# Modular_RFPA_v106.net
KiCad netlist of a schematic drawn in EAGLE
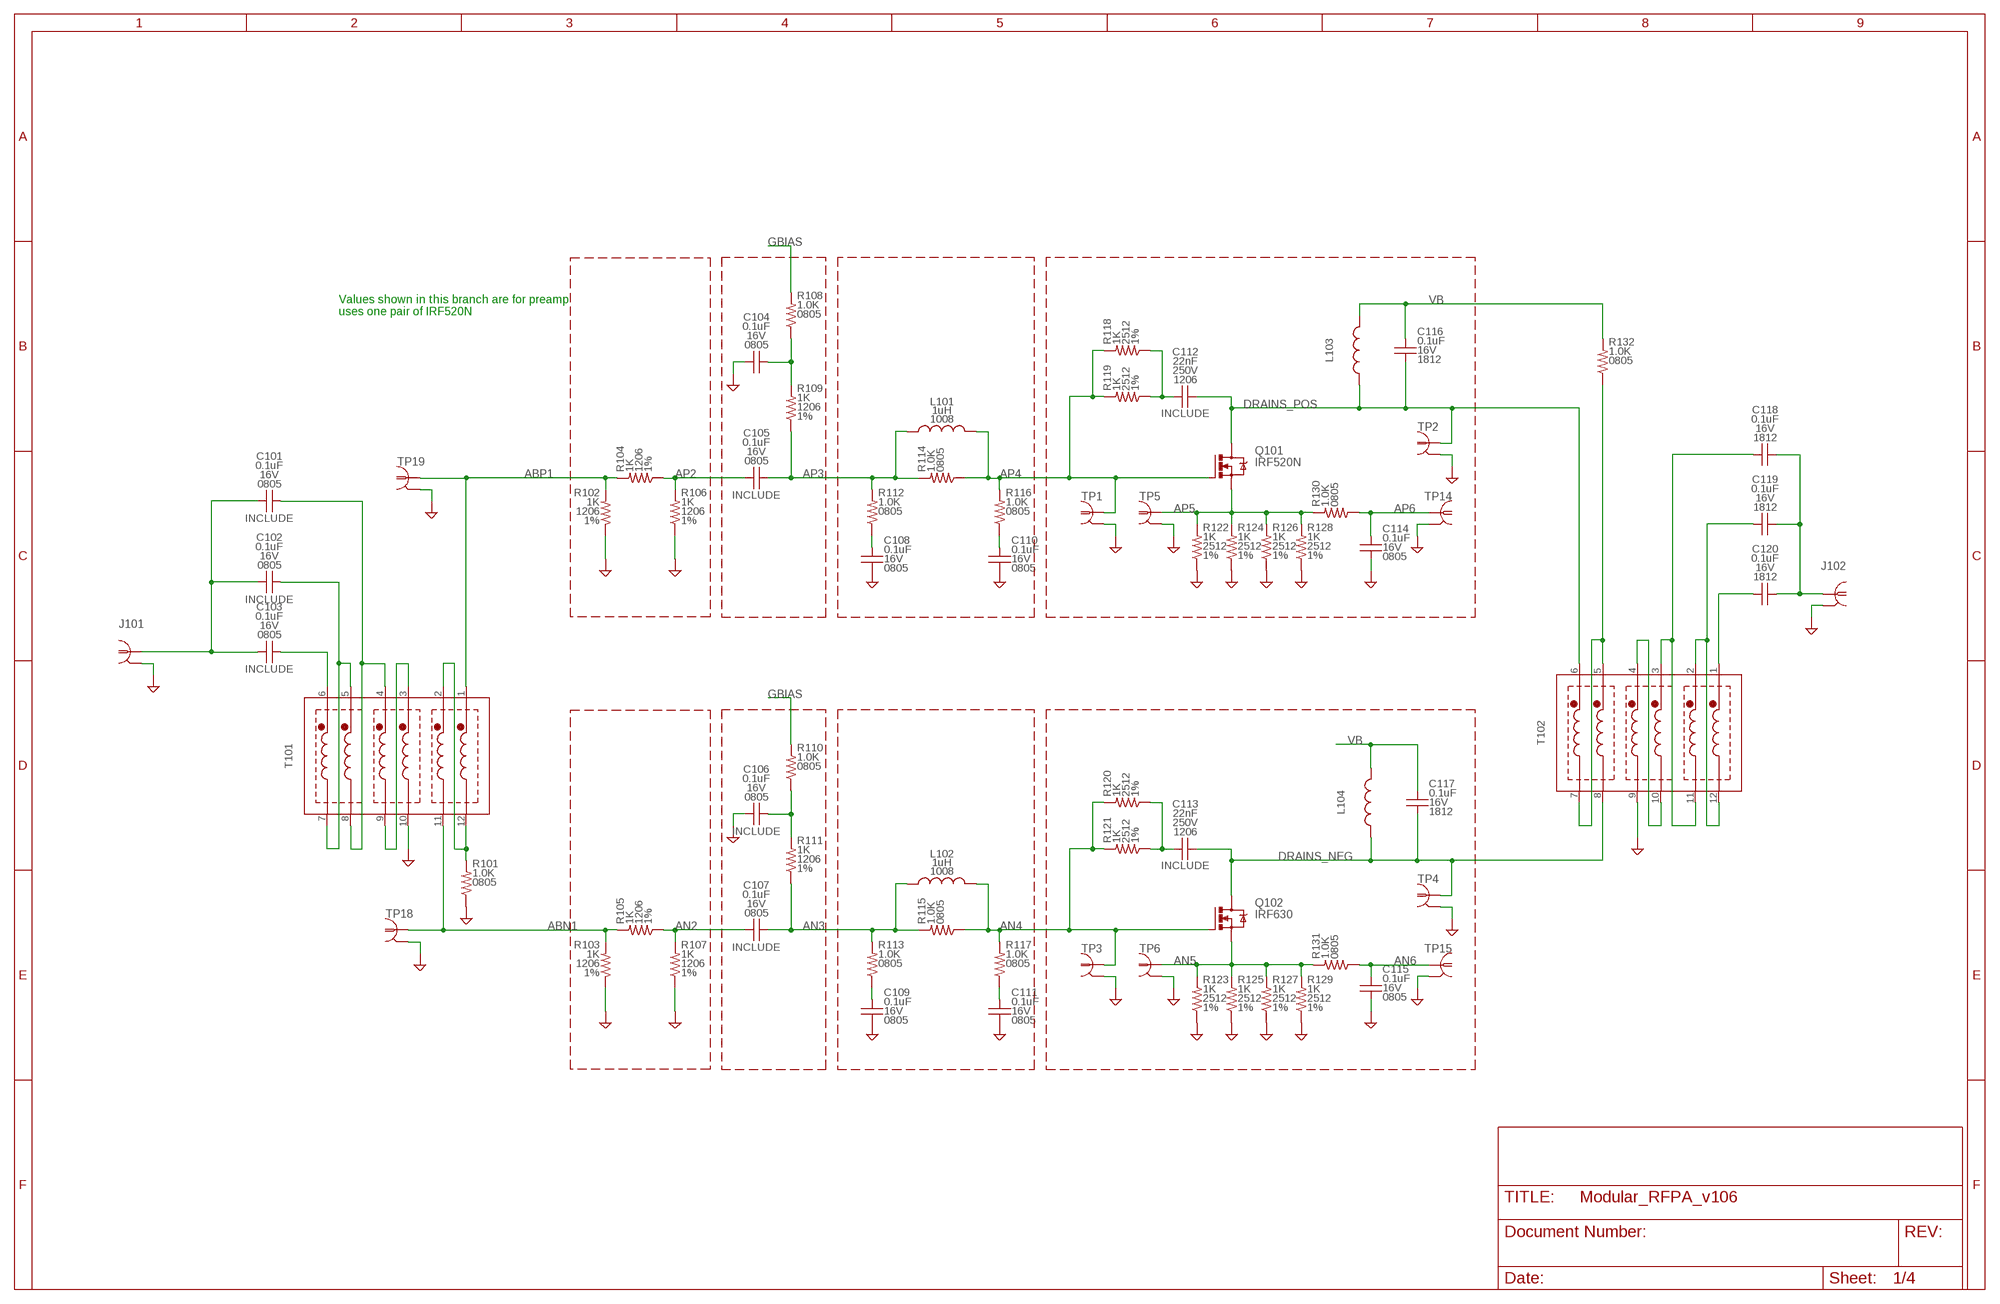
[diagram p0: schematic, sheet 1, part 1 of 2]
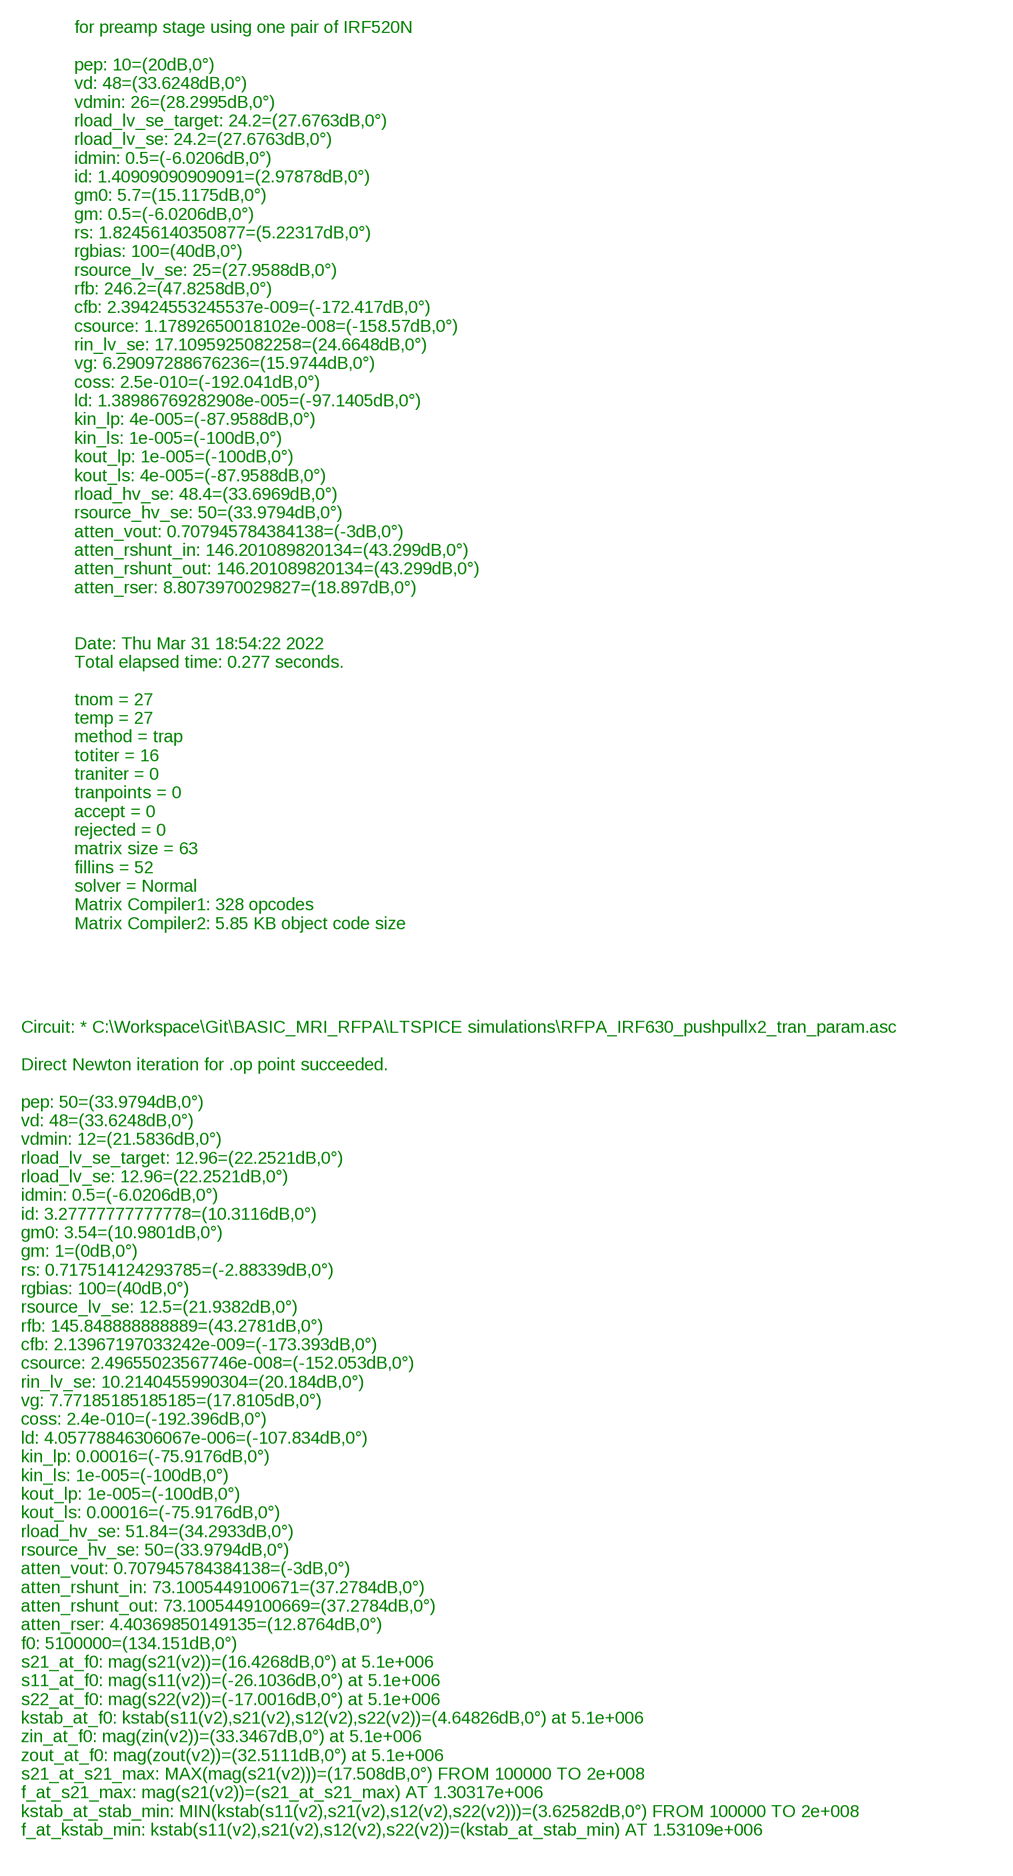
[diagram p1: schematic, sheet 1, part 2 of 2]
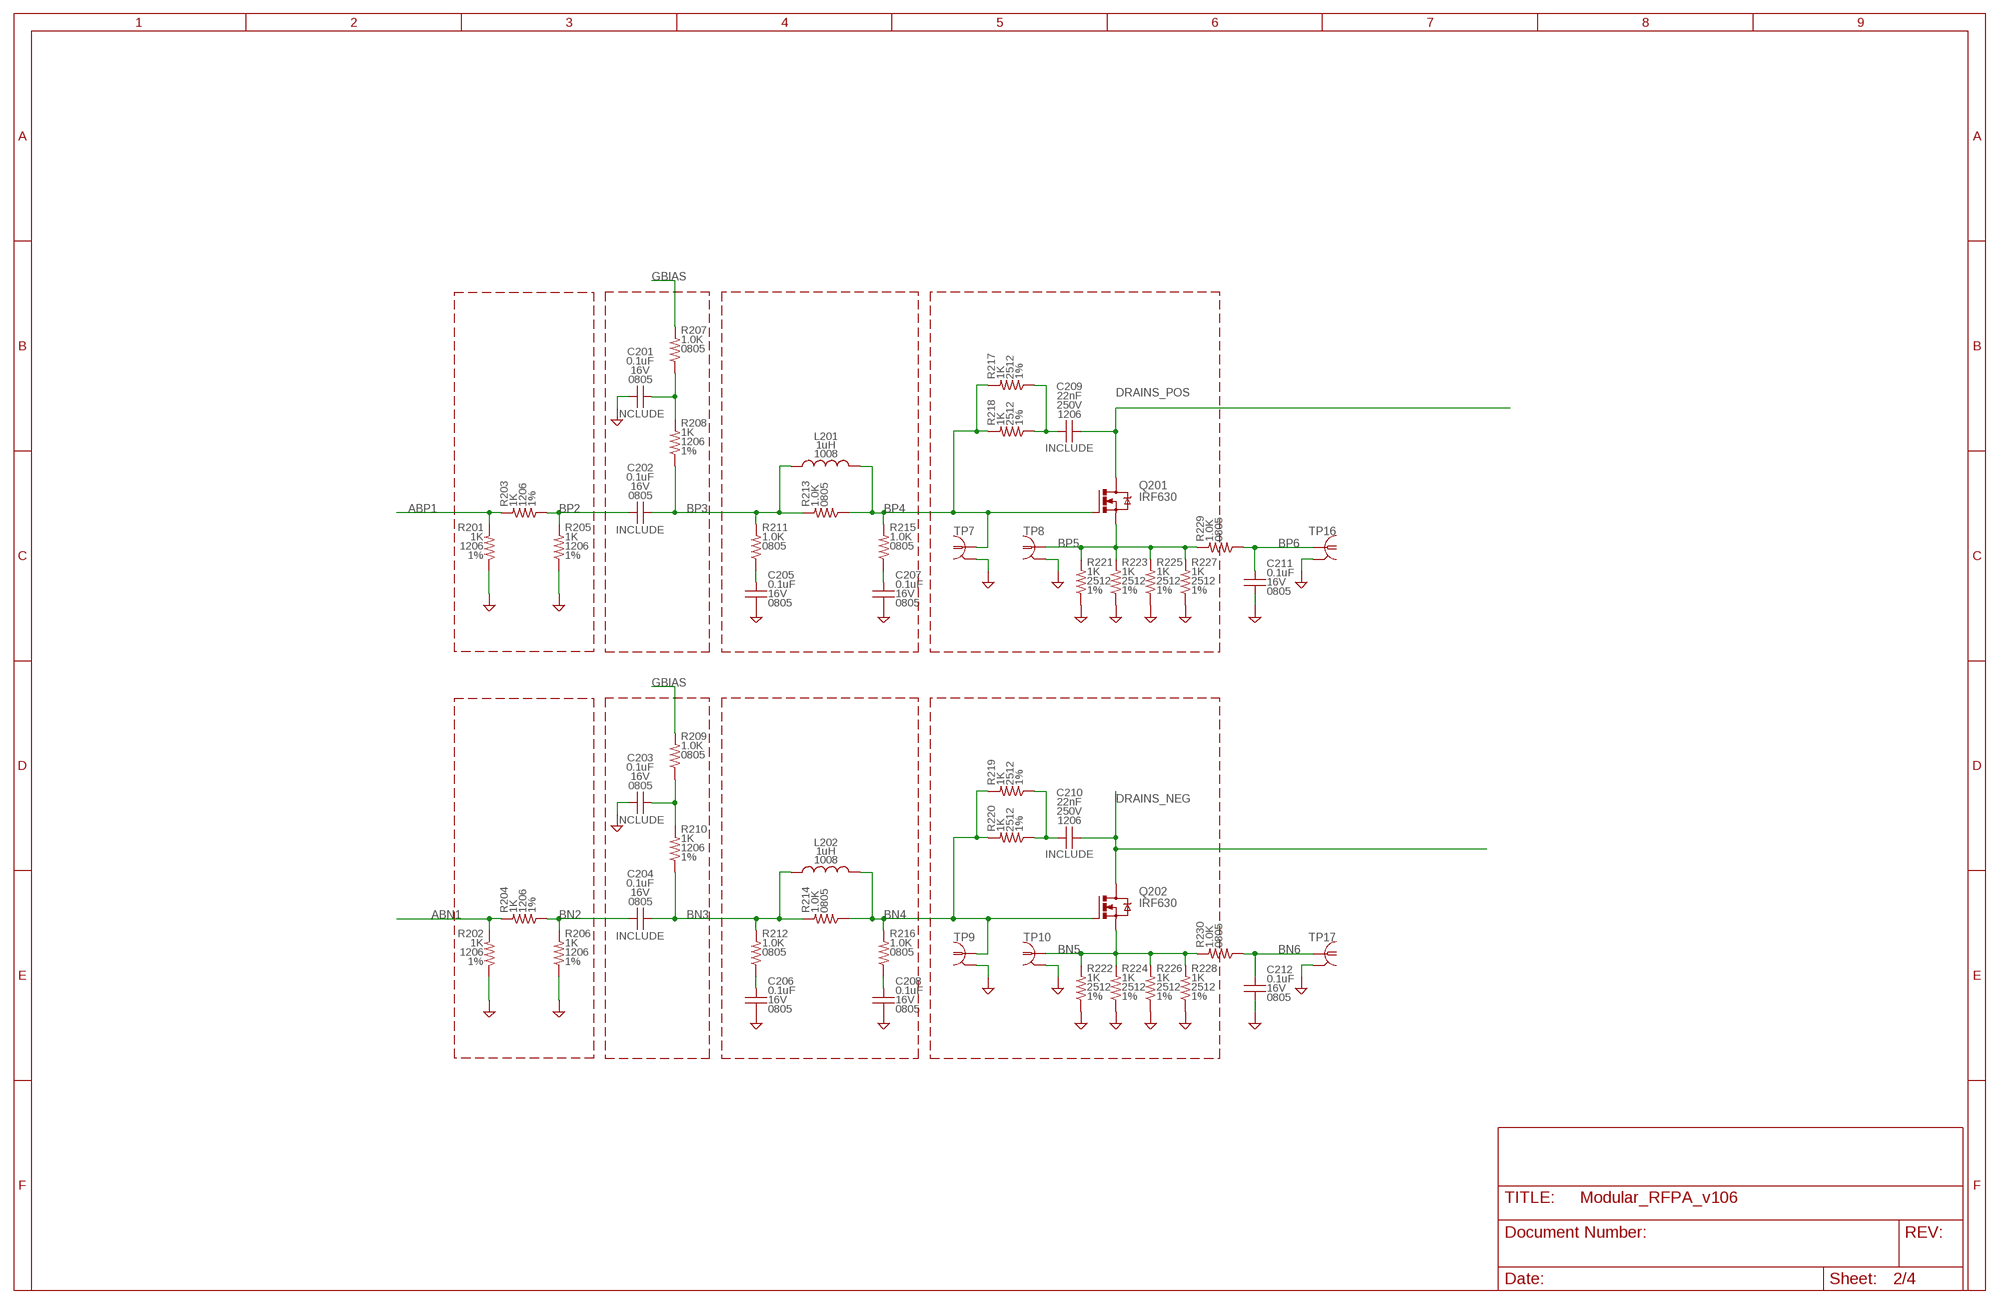
[diagram p2: schematic, sheet 2]
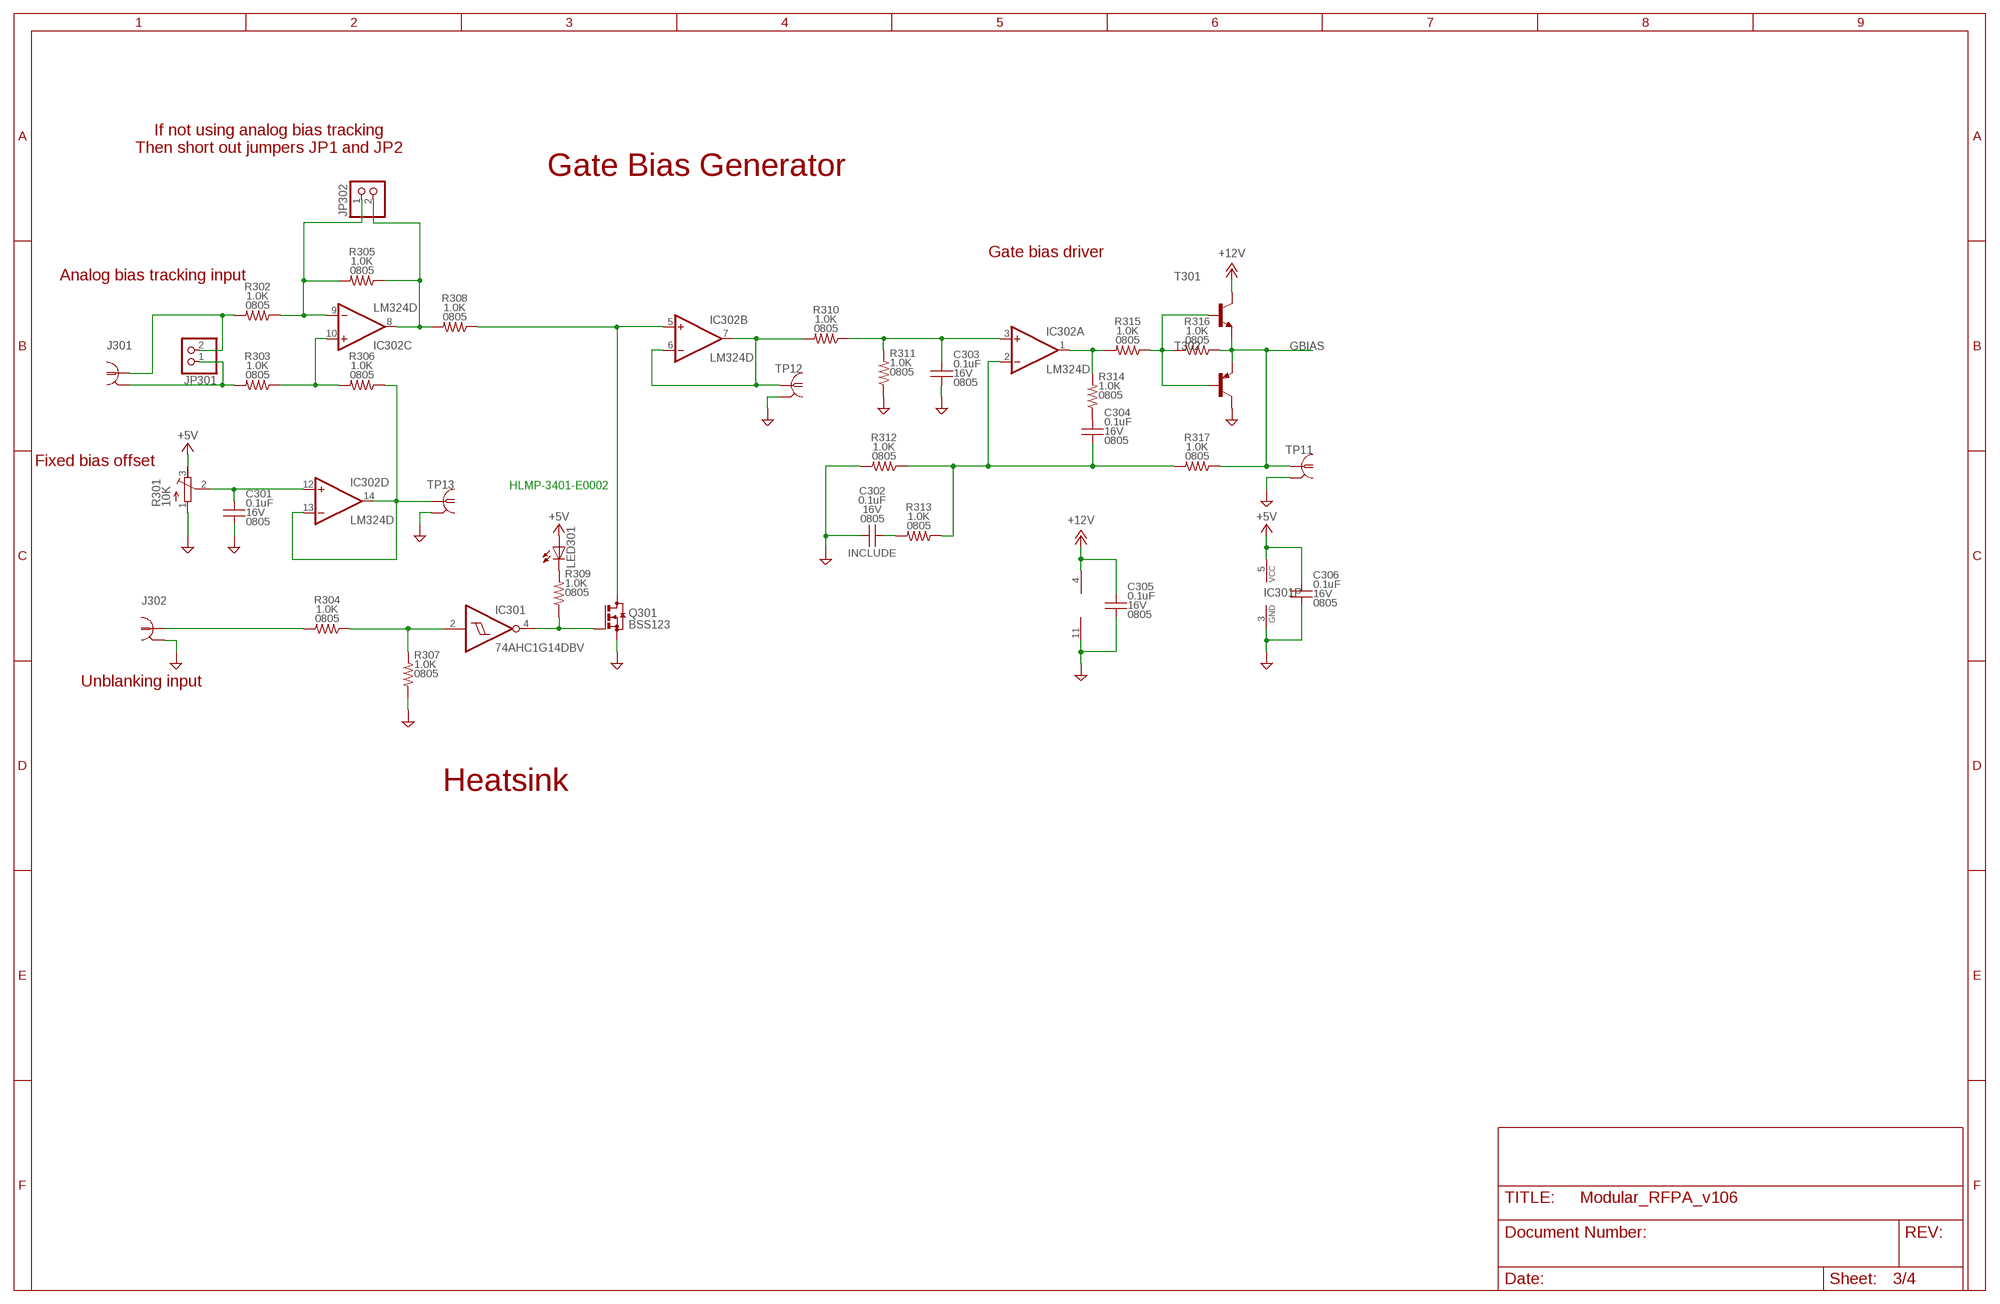
[diagram p3: schematic, sheet 3]
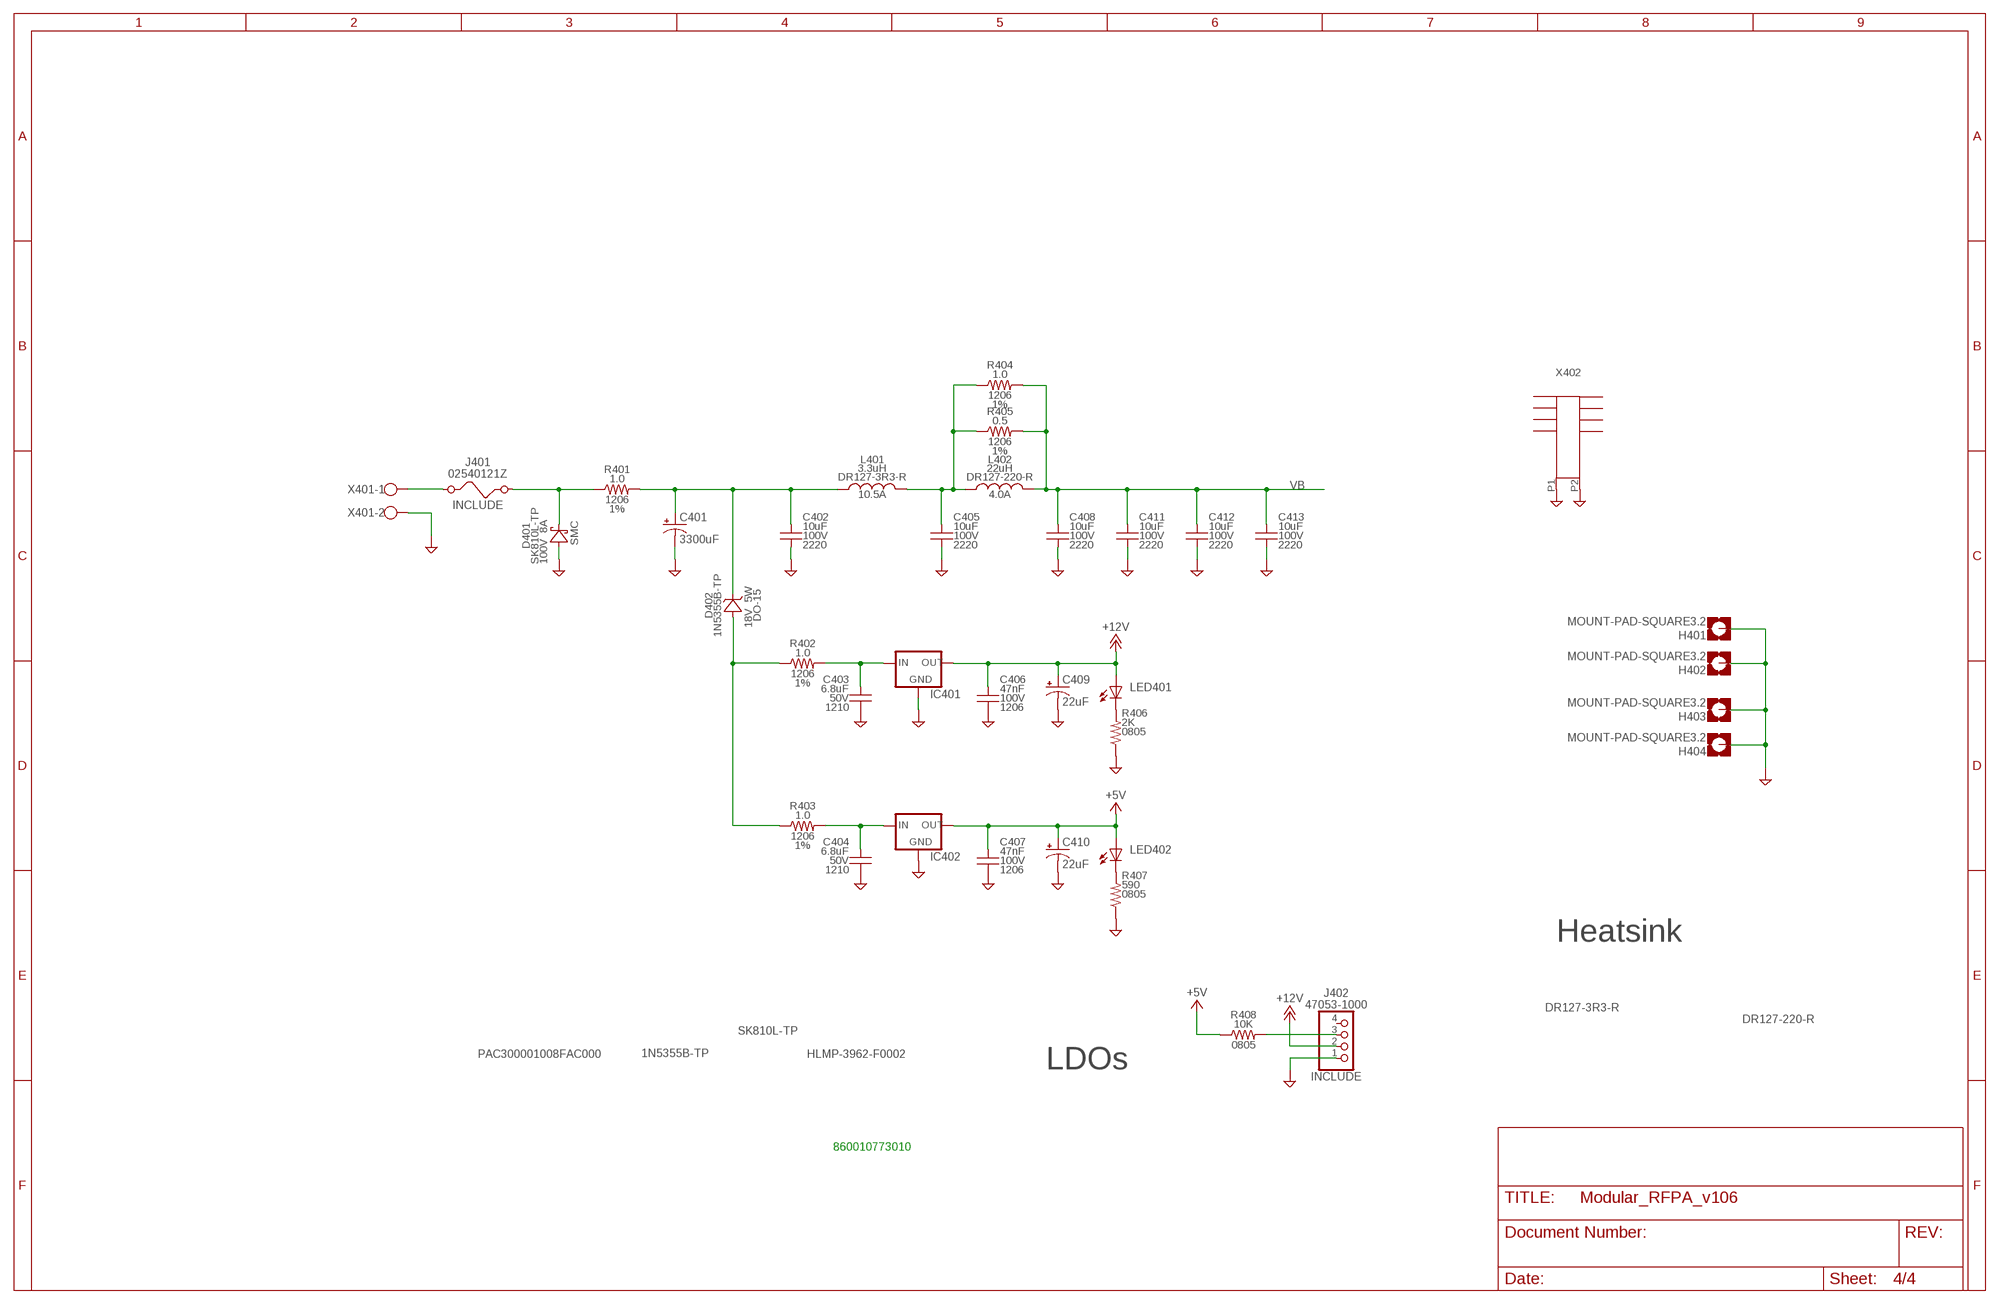
[diagram p4: schematic, sheet 4]

(export (version "E")
  (design (tool "Eeschema 10.0.6"))
  (components
    (comp (ref "C201")
      (value "0.1uF")
      (footprint "eagle-import:0805_IPC-7351B")
      (fields (field (name "PACKAGE") "0805") (field (name "VOLTAGE") "16V") (field (name "BOM") "INCLUDE"))
      (libsource (lib "eagle-import") (part "C0805_IPCC-0.1U-16V-0805-X7R"))
    )
    (comp (ref "C202")
      (value "0.1uF")
      (footprint "eagle-import:0805_IPC-7351B")
      (fields (field (name "PACKAGE") "0805") (field (name "VOLTAGE") "16V") (field (name "BOM") "INCLUDE"))
      (libsource (lib "eagle-import") (part "C0805_IPCC-0.1U-16V-0805-X7R"))
    )
    (comp (ref "C203")
      (value "0.1uF")
      (footprint "eagle-import:0805_IPC-7351B")
      (fields (field (name "PACKAGE") "0805") (field (name "VOLTAGE") "16V") (field (name "BOM") "INCLUDE"))
      (libsource (lib "eagle-import") (part "C0805_IPCC-0.1U-16V-0805-X7R"))
    )
    (comp (ref "C204")
      (value "0.1uF")
      (footprint "eagle-import:0805_IPC-7351B")
      (fields (field (name "PACKAGE") "0805") (field (name "VOLTAGE") "16V") (field (name "BOM") "INCLUDE"))
      (libsource (lib "eagle-import") (part "C0805_IPCC-0.1U-16V-0805-X7R"))
    )
    (comp (ref "C205")
      (value "0.1uF")
      (footprint "eagle-import:0805_IPC-7351B")
      (fields (field (name "VOLTAGE") "16V"))
      (libsource (lib "eagle-import") (part "C0805_IPCC-0.1U-16V-0805-X7R"))
    )
    (comp (ref "C206")
      (value "0.1uF")
      (footprint "eagle-import:0805_IPC-7351B")
      (fields (field (name "VOLTAGE") "16V"))
      (libsource (lib "eagle-import") (part "C0805_IPCC-0.1U-16V-0805-X7R"))
    )
    (comp (ref "C207")
      (value "0.1uF")
      (footprint "eagle-import:0805_IPC-7351B")
      (fields (field (name "VOLTAGE") "16V"))
      (libsource (lib "eagle-import") (part "C0805_IPCC-0.1U-16V-0805-X7R"))
    )
    (comp (ref "C208")
      (value "0.1uF")
      (footprint "eagle-import:0805_IPC-7351B")
      (fields (field (name "VOLTAGE") "16V"))
      (libsource (lib "eagle-import") (part "C0805_IPCC-0.1U-16V-0805-X7R"))
    )
    (comp (ref "C209")
      (value "22nF")
      (footprint "eagle-import:C1206")
      (fields
        (field (name "BOM") "INCLUDE")
        (field (name "PACKAGE") "1206")
        (field (name "PARTNO") "C3216NP02E223J160AA")
        (field (name "VOLTAGE") "250V")
      )
      (libsource (lib "eagle-import") (part "CC1206C-22N-250V-5%-1206-NP0"))
    )
    (comp (ref "C210")
      (value "22nF")
      (footprint "eagle-import:C1206")
      (fields
        (field (name "BOM") "INCLUDE")
        (field (name "PACKAGE") "1206")
        (field (name "PARTNO") "C3216NP02E223J160AA")
        (field (name "VOLTAGE") "250V")
      )
      (libsource (lib "eagle-import") (part "CC1206C-22N-250V-5%-1206-NP0"))
    )
    (comp (ref "C211")
      (value "0.1uF")
      (footprint "eagle-import:0805_IPC-7351B")
      (fields (field (name "VOLTAGE") "16V"))
      (libsource (lib "eagle-import") (part "C0805_IPCC-0.1U-16V-0805-X7R"))
    )
    (comp (ref "C212")
      (value "0.1uF")
      (footprint "eagle-import:0805_IPC-7351B")
      (fields (field (name "VOLTAGE") "16V"))
      (libsource (lib "eagle-import") (part "C0805_IPCC-0.1U-16V-0805-X7R"))
    )
    (comp (ref "L201")
      (value "1uH")
      (footprint "eagle-import:L1008")
      (fields (field (name "PARTNO") "1008CS-102XJEC"))
      (libsource (lib "eagle-import") (part "L_CHIP1008L-1.0U-AIR-5%-1008-0.37A"))
    )
    (comp (ref "L202")
      (value "1uH")
      (footprint "eagle-import:L1008")
      (fields (field (name "PARTNO") "1008CS-102XJEC"))
      (libsource (lib "eagle-import") (part "L_CHIP1008L-1.0U-AIR-5%-1008-0.37A"))
    )
    (comp (ref "Q201")
      (value "IRF630")
      (footprint "eagle-import:TO220BV")
      (libsource (lib "eagle-import") (part "IRF540"))
    )
    (comp (ref "Q202")
      (value "IRF630")
      (footprint "eagle-import:TO220BV")
      (libsource (lib "eagle-import") (part "IRF540"))
    )
    (comp (ref "R201")
      (value "1K")
      (footprint "eagle-import:R1206")
      (fields (field (name "POWER") "0.25"))
      (libsource (lib "eagle-import") (part "RR1206R-1.0K-1%-1206-0.25W"))
    )
    (comp (ref "R202")
      (value "1K")
      (footprint "eagle-import:R1206")
      (fields (field (name "POWER") "0.25"))
      (libsource (lib "eagle-import") (part "RR1206R-1.0K-1%-1206-0.25W"))
    )
    (comp (ref "R203")
      (value "1K")
      (footprint "eagle-import:R1206")
      (fields (field (name "POWER") "0.25"))
      (libsource (lib "eagle-import") (part "RR1206R-1.0K-1%-1206-0.25W"))
    )
    (comp (ref "R204")
      (value "1K")
      (footprint "eagle-import:R1206")
      (fields (field (name "POWER") "0.25"))
      (libsource (lib "eagle-import") (part "RR1206R-1.0K-1%-1206-0.25W"))
    )
    (comp (ref "R205")
      (value "1K")
      (footprint "eagle-import:R1206")
      (fields (field (name "POWER") "0.25"))
      (libsource (lib "eagle-import") (part "RR1206R-1.0K-1%-1206-0.25W"))
    )
    (comp (ref "R206")
      (value "1K")
      (footprint "eagle-import:R1206")
      (fields (field (name "POWER") "0.25"))
      (libsource (lib "eagle-import") (part "RR1206R-1.0K-1%-1206-0.25W"))
    )
    (comp (ref "R207")
      (value "1.0K")
      (footprint "eagle-import:0805_IPC-7351B")
      (libsource (lib "eagle-import") (part "R0805_IPCR-1.0K-0.1%-0805-0.1W"))
    )
    (comp (ref "R208")
      (value "1K")
      (footprint "eagle-import:R1206")
      (fields (field (name "POWER") "0.25"))
      (libsource (lib "eagle-import") (part "RR1206R-1.0K-1%-1206-0.25W"))
    )
    (comp (ref "R209")
      (value "1.0K")
      (footprint "eagle-import:0805_IPC-7351B")
      (libsource (lib "eagle-import") (part "R0805_IPCR-1.0K-0.1%-0805-0.1W"))
    )
    (comp (ref "R210")
      (value "1K")
      (footprint "eagle-import:R1206")
      (fields (field (name "POWER") "0.25"))
      (libsource (lib "eagle-import") (part "RR1206R-1.0K-1%-1206-0.25W"))
    )
    (comp (ref "R211")
      (value "1.0K")
      (footprint "eagle-import:0805_IPC-7351B")
      (libsource (lib "eagle-import") (part "R0805_IPCR-1.0K-0.1%-0805-0.1W"))
    )
    (comp (ref "R212")
      (value "1.0K")
      (footprint "eagle-import:0805_IPC-7351B")
      (libsource (lib "eagle-import") (part "R0805_IPCR-1.0K-0.1%-0805-0.1W"))
    )
    (comp (ref "R213")
      (value "1.0K")
      (footprint "eagle-import:0805_IPC-7351B")
      (libsource (lib "eagle-import") (part "R0805_IPCR-1.0K-0.1%-0805-0.1W"))
    )
    (comp (ref "R214")
      (value "1.0K")
      (footprint "eagle-import:0805_IPC-7351B")
      (libsource (lib "eagle-import") (part "R0805_IPCR-1.0K-0.1%-0805-0.1W"))
    )
    (comp (ref "R215")
      (value "1.0K")
      (footprint "eagle-import:0805_IPC-7351B")
      (libsource (lib "eagle-import") (part "R0805_IPCR-1.0K-0.1%-0805-0.1W"))
    )
    (comp (ref "R216")
      (value "1.0K")
      (footprint "eagle-import:0805_IPC-7351B")
      (libsource (lib "eagle-import") (part "R0805_IPCR-1.0K-0.1%-0805-0.1W"))
    )
    (comp (ref "R217")
      (value "1K")
      (footprint "eagle-import:R2512")
      (fields (field (name "POWER") "1"))
      (libsource (lib "eagle-import") (part "RR2512R-1K-1%-2512-1W"))
    )
    (comp (ref "R218")
      (value "1K")
      (footprint "eagle-import:R2512")
      (fields (field (name "POWER") "1"))
      (libsource (lib "eagle-import") (part "RR2512R-1K-1%-2512-1W"))
    )
    (comp (ref "R219")
      (value "1K")
      (footprint "eagle-import:R2512")
      (fields (field (name "POWER") "1"))
      (libsource (lib "eagle-import") (part "RR2512R-1K-1%-2512-1W"))
    )
    (comp (ref "R220")
      (value "1K")
      (footprint "eagle-import:R2512")
      (fields (field (name "POWER") "1"))
      (libsource (lib "eagle-import") (part "RR2512R-1K-1%-2512-1W"))
    )
    (comp (ref "R221")
      (value "1K")
      (footprint "eagle-import:R2512")
      (fields (field (name "POWER") "1"))
      (libsource (lib "eagle-import") (part "RR2512R-1K-1%-2512-1W"))
    )
    (comp (ref "R222")
      (value "1K")
      (footprint "eagle-import:R2512")
      (fields (field (name "POWER") "1"))
      (libsource (lib "eagle-import") (part "RR2512R-1K-1%-2512-1W"))
    )
    (comp (ref "R223")
      (value "1K")
      (footprint "eagle-import:R2512")
      (fields (field (name "POWER") "1"))
      (libsource (lib "eagle-import") (part "RR2512R-1K-1%-2512-1W"))
    )
    (comp (ref "R224")
      (value "1K")
      (footprint "eagle-import:R2512")
      (fields (field (name "POWER") "1"))
      (libsource (lib "eagle-import") (part "RR2512R-1K-1%-2512-1W"))
    )
    (comp (ref "R225")
      (value "1K")
      (footprint "eagle-import:R2512")
      (fields (field (name "POWER") "1"))
      (libsource (lib "eagle-import") (part "RR2512R-1K-1%-2512-1W"))
    )
    (comp (ref "R226")
      (value "1K")
      (footprint "eagle-import:R2512")
      (fields (field (name "POWER") "1"))
      (libsource (lib "eagle-import") (part "RR2512R-1K-1%-2512-1W"))
    )
    (comp (ref "R227")
      (value "1K")
      (footprint "eagle-import:R2512")
      (fields (field (name "POWER") "1"))
      (libsource (lib "eagle-import") (part "RR2512R-1K-1%-2512-1W"))
    )
    (comp (ref "R228")
      (value "1K")
      (footprint "eagle-import:R2512")
      (fields (field (name "POWER") "1"))
      (libsource (lib "eagle-import") (part "RR2512R-1K-1%-2512-1W"))
    )
    (comp (ref "R229")
      (value "1.0K")
      (footprint "eagle-import:0805_IPC-7351B")
      (libsource (lib "eagle-import") (part "R0805_IPCR-1.0K-0.1%-0805-0.1W"))
    )
    (comp (ref "R230")
      (value "1.0K")
      (footprint "eagle-import:0805_IPC-7351B")
      (libsource (lib "eagle-import") (part "R0805_IPCR-1.0K-0.1%-0805-0.1W"))
    )
    (comp (ref "TP7")
      (value "PROBE_TPTP_5MM")
      (footprint "eagle-import:PROBE_TP_5MM")
      (libsource (lib "eagle-import") (part "PROBE_TPTP_5MM"))
    )
    (comp (ref "TP8")
      (value "PROBE_TPTP_7P5MM")
      (footprint "eagle-import:PROBE_TP_7P5MM")
      (libsource (lib "eagle-import") (part "PROBE_TPTP_7P5MM"))
    )
    (comp (ref "TP9")
      (value "PROBE_TPTP_5MM")
      (footprint "eagle-import:PROBE_TP_5MM")
      (libsource (lib "eagle-import") (part "PROBE_TPTP_5MM"))
    )
    (comp (ref "TP10")
      (value "PROBE_TPTP_5MM")
      (footprint "eagle-import:PROBE_TP_5MM")
      (libsource (lib "eagle-import") (part "PROBE_TPTP_5MM"))
    )
    (comp (ref "TP16")
      (value "PROBE_TPTP_5MM")
      (footprint "eagle-import:PROBE_TP_5MM")
      (libsource (lib "eagle-import") (part "PROBE_TPTP_5MM"))
    )
    (comp (ref "TP17")
      (value "PROBE_TPTP_7P5MM")
      (footprint "eagle-import:PROBE_TP_7P5MM")
      (libsource (lib "eagle-import") (part "PROBE_TPTP_7P5MM"))
    )
    (comp (ref "C301")
      (value "0.1uF")
      (footprint "eagle-import:0805_IPC-7351B")
      (fields (field (name "VOLTAGE") "16V"))
      (libsource (lib "eagle-import") (part "C0805_IPCC-0.1U-16V-0805-X7R"))
    )
    (comp (ref "C302")
      (value "0.1uF")
      (footprint "eagle-import:0805_IPC-7351B")
      (fields (field (name "PACKAGE") "0805") (field (name "VOLTAGE") "16V") (field (name "BOM") "INCLUDE"))
      (libsource (lib "eagle-import") (part "C0805_IPCC-0.1U-16V-0805-X7R"))
    )
    (comp (ref "C303")
      (value "0.1uF")
      (footprint "eagle-import:0805_IPC-7351B")
      (fields (field (name "VOLTAGE") "16V"))
      (libsource (lib "eagle-import") (part "C0805_IPCC-0.1U-16V-0805-X7R"))
    )
    (comp (ref "C304")
      (value "0.1uF")
      (footprint "eagle-import:0805_IPC-7351B")
      (fields (field (name "VOLTAGE") "16V"))
      (libsource (lib "eagle-import") (part "C0805_IPCC-0.1U-16V-0805-X7R"))
    )
    (comp (ref "C305")
      (value "0.1uF")
      (footprint "eagle-import:0805_IPC-7351B")
      (fields (field (name "VOLTAGE") "16V"))
      (libsource (lib "eagle-import") (part "C0805_IPCC-0.1U-16V-0805-X7R"))
    )
    (comp (ref "C306")
      (value "0.1uF")
      (footprint "eagle-import:0805_IPC-7351B")
      (fields (field (name "VOLTAGE") "16V"))
      (libsource (lib "eagle-import") (part "C0805_IPCC-0.1U-16V-0805-X7R"))
    )
    (comp (ref "IC301")
      (value "74AHC1G14DBV")
      (footprint "eagle-import:SOT23-5")
      (libsource (lib "eagle-import") (part "741G14DBVAHC"))
    )
    (comp (ref "IC302")
      (value "LM324D")
      (footprint "eagle-import:SO14")
      (libsource (lib "eagle-import") (part "LM324D"))
    )
    (comp (ref "J301")
      (value "COAXBNC_EDGE")
      (footprint "eagle-import:BNC_EDGE")
      (libsource (lib "eagle-import") (part "COAXBNC_EDGE"))
    )
    (comp (ref "J302")
      (value "COAXBNC_EDGE")
      (footprint "eagle-import:BNC_EDGE")
      (libsource (lib "eagle-import") (part "COAXBNC_EDGE"))
    )
    (comp (ref "JP301")
      (value "PINHD-1X2")
      (footprint "eagle-import:1X02")
      (libsource (lib "eagle-import") (part "PINHD-1X2"))
    )
    (comp (ref "JP302")
      (value "PINHD-1X2")
      (footprint "eagle-import:1X02")
      (libsource (lib "eagle-import") (part "PINHD-1X2"))
    )
    (comp (ref "LED301")
      (value "LED5MM")
      (footprint "eagle-import:LED5MM")
      (libsource (lib "eagle-import") (part "LED5MM"))
    )
    (comp (ref "Q301")
      (value "BSS123")
      (footprint "eagle-import:SOT23")
      (libsource (lib "eagle-import") (part "BSS123"))
    )
    (comp (ref "R301")
      (value "10K")
      (footprint "eagle-import:RTRIM3299W")
      (libsource (lib "eagle-import") (part "R-TRIMM3299W"))
    )
    (comp (ref "R302")
      (value "1.0K")
      (footprint "eagle-import:0805_IPC-7351B")
      (fields (field (name "PACKAGE") "0805"))
      (libsource (lib "eagle-import") (part "R0805_IPCR-1.0K-0.1%-0805-0.1W"))
    )
    (comp (ref "R303")
      (value "1.0K")
      (footprint "eagle-import:0805_IPC-7351B")
      (fields (field (name "PACKAGE") "0805"))
      (libsource (lib "eagle-import") (part "R0805_IPCR-1.0K-0.1%-0805-0.1W"))
    )
    (comp (ref "R304")
      (value "1.0K")
      (footprint "eagle-import:0805_IPC-7351B")
      (fields (field (name "PACKAGE") "0805"))
      (libsource (lib "eagle-import") (part "R0805_IPCR-1.0K-0.1%-0805-0.1W"))
    )
    (comp (ref "R305")
      (value "1.0K")
      (footprint "eagle-import:0805_IPC-7351B")
      (fields (field (name "PACKAGE") "0805"))
      (libsource (lib "eagle-import") (part "R0805_IPCR-1.0K-0.1%-0805-0.1W"))
    )
    (comp (ref "R306")
      (value "1.0K")
      (footprint "eagle-import:0805_IPC-7351B")
      (fields (field (name "PACKAGE") "0805"))
      (libsource (lib "eagle-import") (part "R0805_IPCR-1.0K-0.1%-0805-0.1W"))
    )
    (comp (ref "R307")
      (value "1.0K")
      (footprint "eagle-import:0805_IPC-7351B")
      (libsource (lib "eagle-import") (part "R0805_IPCR-1.0K-0.1%-0805-0.1W"))
    )
    (comp (ref "R308")
      (value "1.0K")
      (footprint "eagle-import:0805_IPC-7351B")
      (fields (field (name "PACKAGE") "0805"))
      (libsource (lib "eagle-import") (part "R0805_IPCR-1.0K-0.1%-0805-0.1W"))
    )
    (comp (ref "R309")
      (value "1.0K")
      (footprint "eagle-import:0805_IPC-7351B")
      (libsource (lib "eagle-import") (part "R0805_IPCR-1.0K-0.1%-0805-0.1W"))
    )
    (comp (ref "R310")
      (value "1.0K")
      (footprint "eagle-import:0805_IPC-7351B")
      (fields (field (name "PACKAGE") "0805"))
      (libsource (lib "eagle-import") (part "R0805_IPCR-1.0K-0.1%-0805-0.1W"))
    )
    (comp (ref "R311")
      (value "1.0K")
      (footprint "eagle-import:0805_IPC-7351B")
      (libsource (lib "eagle-import") (part "R0805_IPCR-1.0K-0.1%-0805-0.1W"))
    )
    (comp (ref "R312")
      (value "1.0K")
      (footprint "eagle-import:0805_IPC-7351B")
      (fields (field (name "PACKAGE") "0805"))
      (libsource (lib "eagle-import") (part "R0805_IPCR-1.0K-0.1%-0805-0.1W"))
    )
    (comp (ref "R313")
      (value "1.0K")
      (footprint "eagle-import:0805_IPC-7351B")
      (fields (field (name "PACKAGE") "0805"))
      (libsource (lib "eagle-import") (part "R0805_IPCR-1.0K-0.1%-0805-0.1W"))
    )
    (comp (ref "R314")
      (value "1.0K")
      (footprint "eagle-import:0805_IPC-7351B")
      (libsource (lib "eagle-import") (part "R0805_IPCR-1.0K-0.1%-0805-0.1W"))
    )
    (comp (ref "R315")
      (value "1.0K")
      (footprint "eagle-import:0805_IPC-7351B")
      (fields (field (name "PACKAGE") "0805"))
      (libsource (lib "eagle-import") (part "R0805_IPCR-1.0K-0.1%-0805-0.1W"))
    )
    (comp (ref "R316")
      (value "1.0K")
      (footprint "eagle-import:0805_IPC-7351B")
      (fields (field (name "PACKAGE") "0805"))
      (libsource (lib "eagle-import") (part "R0805_IPCR-1.0K-0.1%-0805-0.1W"))
    )
    (comp (ref "R317")
      (value "1.0K")
      (footprint "eagle-import:0805_IPC-7351B")
      (fields (field (name "PACKAGE") "0805"))
      (libsource (lib "eagle-import") (part "R0805_IPCR-1.0K-0.1%-0805-0.1W"))
    )
    (comp (ref "T301")
      (value "BC808-NPN-SOT23-BEC")
      (footprint "eagle-import:SOT23-BEC")
      (libsource (lib "eagle-import") (part "-NPN-SOT23-BECBC808"))
    )
    (comp (ref "T302")
      (value "BC807-16-PNP-SOT23-BEC")
      (footprint "eagle-import:SOT23-BEC")
      (libsource (lib "eagle-import") (part "-PNP-SOT23-BECBC807-16"))
    )
    (comp (ref "TP11")
      (value "PROBE_TPTP_5MM")
      (footprint "eagle-import:PROBE_TP_5MM")
      (libsource (lib "eagle-import") (part "PROBE_TPTP_5MM"))
    )
    (comp (ref "TP12")
      (value "PROBE_TPTP_5MM")
      (footprint "eagle-import:PROBE_TP_5MM")
      (libsource (lib "eagle-import") (part "PROBE_TPTP_5MM"))
    )
    (comp (ref "TP13")
      (value "PROBE_TPTP_5MM")
      (footprint "eagle-import:PROBE_TP_5MM")
      (libsource (lib "eagle-import") (part "PROBE_TPTP_5MM"))
    )
    (comp (ref "C401")
      (value "3300uF")
      (footprint "eagle-import:EB25D")
      (libsource (lib "eagle-import") (part "CPOL-USE10-25"))
    )
    (comp (ref "C402")
      (value "10uF")
      (footprint "eagle-import:C2220_CKG57N")
      (fields
        (field (name "BOM") "INCLUDE")
        (field (name "PACKAGE") "2220")
        (field (name "PARTNO") "CGA9N3X7S2A106M230KE")
        (field (name "VOLTAGE") "100V")
      )
      (libsource (lib "eagle-import") (part "CC2220_CKG57NCC-10U-100V-20%-2220-X7T"))
    )
    (comp (ref "C403")
      (value "6.8uF")
      (footprint "eagle-import:C1210")
      (fields (field (name "PARTNO") "CGA6P3X7S1H685K250AB") (field (name "VOLTAGE") "50V"))
      (libsource (lib "eagle-import") (part "CC1210CC-6.8U-50V-10%-1210-X7S"))
    )
    (comp (ref "C404")
      (value "6.8uF")
      (footprint "eagle-import:C1210")
      (fields (field (name "PARTNO") "CGA6P3X7S1H685K250AB") (field (name "VOLTAGE") "50V"))
      (libsource (lib "eagle-import") (part "CC1210CC-6.8U-50V-10%-1210-X7S"))
    )
    (comp (ref "C405")
      (value "10uF")
      (footprint "eagle-import:C2220_CKG57N")
      (fields
        (field (name "BOM") "INCLUDE")
        (field (name "PACKAGE") "2220")
        (field (name "PARTNO") "CGA9N3X7S2A106M230KE")
        (field (name "VOLTAGE") "100V")
      )
      (libsource (lib "eagle-import") (part "CC2220_CKG57NCC-10U-100V-20%-2220-X7T"))
    )
    (comp (ref "C406")
      (value "47nF")
      (footprint "eagle-import:C1206")
      (fields (field (name "PARTNO") "C3216C0G2A473J115AC") (field (name "VOLTAGE") "100V"))
      (libsource (lib "eagle-import") (part "CC1206C-47N-100V-5%-1206-NP0"))
    )
    (comp (ref "C407")
      (value "47nF")
      (footprint "eagle-import:C1206")
      (fields (field (name "PARTNO") "C3216C0G2A473J115AC") (field (name "VOLTAGE") "100V"))
      (libsource (lib "eagle-import") (part "CC1206C-47N-100V-5%-1206-NP0"))
    )
    (comp (ref "C408")
      (value "10uF")
      (footprint "eagle-import:C2220_CKG57N")
      (fields (field (name "PARTNO") "CGA9N3X7S2A106M230KE") (field (name "VOLTAGE") "100V"))
      (libsource (lib "eagle-import") (part "CC2220_CKG57NCC-10U-100V-20%-2220-X7T"))
    )
    (comp (ref "C409")
      (value "22uF")
      (footprint "eagle-import:E2,5-7")
      (libsource (lib "eagle-import") (part "CPOL-USE2.5-7"))
    )
    (comp (ref "C410")
      (value "22uF")
      (footprint "eagle-import:E2,5-7")
      (libsource (lib "eagle-import") (part "CPOL-USE2.5-7"))
    )
    (comp (ref "C411")
      (value "10uF")
      (footprint "eagle-import:C2220_CKG57N")
      (fields (field (name "PARTNO") "CGA9N3X7S2A106M230KE") (field (name "VOLTAGE") "100V"))
      (libsource (lib "eagle-import") (part "CC2220_CKG57NCC-10U-100V-20%-2220-X7T"))
    )
    (comp (ref "C412")
      (value "10uF")
      (footprint "eagle-import:C2220_CKG57N")
      (fields (field (name "PARTNO") "CGA9N3X7S2A106M230KE") (field (name "VOLTAGE") "100V"))
      (libsource (lib "eagle-import") (part "CC2220_CKG57NCC-10U-100V-20%-2220-X7T"))
    )
    (comp (ref "C413")
      (value "10uF")
      (footprint "eagle-import:C2220_CKG57N")
      (fields (field (name "PARTNO") "CGA9N3X7S2A106M230KE") (field (name "VOLTAGE") "100V"))
      (libsource (lib "eagle-import") (part "CC2220_CKG57NCC-10U-100V-20%-2220-X7T"))
    )
    (comp (ref "D401")
      (value "D-SCHOTTKYSK810L-TPSMC")
      (footprint "eagle-import:DO-214AB(SMC)")
      (fields (field (name "PARTNO") "SK810L-TP") (field (name "VOLTAGE") "100V"))
      (libsource (lib "eagle-import") (part "D-SCHOTTKYSMCSK810L-TP"))
    )
    (comp (ref "D402")
      (value "D-ZENER1N5355B-TPDO15-12")
      (footprint "eagle-import:DO15-12")
      (fields (field (name "PARTNO") "1N5355B-TP") (field (name "POWER") "5W") (field (name "VOLTAGE") "18V"))
      (libsource (lib "eagle-import") (part "D-ZENERDO15-121N5355B-TP"))
    )
    (comp (ref "H401")
      (value "MOUNT-PAD-SQUARE3.2")
      (footprint "eagle-import:3,2-PAD-SQUARE")
      (libsource (lib "eagle-import") (part "MOUNT-PAD-SQUARE3.2"))
    )
    (comp (ref "H402")
      (value "MOUNT-PAD-SQUARE3.2")
      (footprint "eagle-import:3,2-PAD-SQUARE")
      (libsource (lib "eagle-import") (part "MOUNT-PAD-SQUARE3.2"))
    )
    (comp (ref "H403")
      (value "MOUNT-PAD-SQUARE3.2")
      (footprint "eagle-import:3,2-PAD-SQUARE")
      (libsource (lib "eagle-import") (part "MOUNT-PAD-SQUARE3.2"))
    )
    (comp (ref "H404")
      (value "MOUNT-PAD-SQUARE3.2")
      (footprint "eagle-import:3,2-PAD-SQUARE")
      (libsource (lib "eagle-import") (part "MOUNT-PAD-SQUARE3.2"))
    )
    (comp (ref "IC401")
      (value "78XXS")
      (footprint "eagle-import:78XXS")
      (libsource (lib "eagle-import") (part "78XXS"))
    )
    (comp (ref "IC402")
      (value "78XXS")
      (footprint "eagle-import:78XXS")
      (libsource (lib "eagle-import") (part "78XXS"))
    )
    (comp (ref "J401")
      (value "FUSE_2P")
      (footprint "eagle-import:02540121Z")
      (fields (field (name "PARTNO") "02540121Z"))
      (libsource (lib "eagle-import") (part "FUSE_2P"))
    )
    (comp (ref "J402")
      (value "KK_PCFAN")
      (footprint "eagle-import:47053-1000")
      (fields (field (name "PARTNO") "47053-1000"))
      (libsource (lib "eagle-import") (part "KK_PCFAN"))
    )
    (comp (ref "L401")
      (value "3.3uH")
      (footprint "eagle-import:DR127")
      (fields (field (name "PARTNO") "DR127-3R3-R"))
      (libsource (lib "eagle-import") (part "LL-3.3U-FERRITE-20%-12.5X12.5MM-10.5A"))
    )
    (comp (ref "L402")
      (value "22uH")
      (footprint "eagle-import:DR127")
      (fields (field (name "PARTNO") "DR127-220-R"))
      (libsource (lib "eagle-import") (part "LL-22U-FERRITE-20%-12.5X12.5MM-4A"))
    )
    (comp (ref "LED401")
      (value "LED5MM")
      (footprint "eagle-import:LED5MM")
      (libsource (lib "eagle-import") (part "LED5MM"))
    )
    (comp (ref "LED402")
      (value "LED5MM")
      (footprint "eagle-import:LED5MM")
      (libsource (lib "eagle-import") (part "LED5MM"))
    )
    (comp (ref "R401")
      (value "1.0")
      (footprint "eagle-import:R1206")
      (fields (field (name "POWER") "0.25"))
      (libsource (lib "eagle-import") (part "R90R1206R-1.0K-1%-1206-0.25W"))
    )
    (comp (ref "R402")
      (value "1.0")
      (footprint "eagle-import:R1206")
      (fields (field (name "POWER") "0.25"))
      (libsource (lib "eagle-import") (part "R90R1206R-1.0K-1%-1206-0.25W"))
    )
    (comp (ref "R403")
      (value "1.0")
      (footprint "eagle-import:R1206")
      (fields (field (name "POWER") "0.25"))
      (libsource (lib "eagle-import") (part "R90R1206R-1.0K-1%-1206-0.25W"))
    )
    (comp (ref "R404")
      (value "1.0")
      (footprint "eagle-import:R1206")
      (fields (field (name "POWER") "0.25"))
      (libsource (lib "eagle-import") (part "R90R1206R-1.0K-1%-1206-0.25W"))
    )
    (comp (ref "R405")
      (value "0.5")
      (footprint "eagle-import:R1206")
      (fields (field (name "POWER") "0.25"))
      (libsource (lib "eagle-import") (part "R90R1206R-1.0K-1%-1206-0.25W"))
    )
    (comp (ref "R406")
      (value "2K")
      (footprint "eagle-import:0805_IPC-7351B")
      (libsource (lib "eagle-import") (part "R0805_IPCR-1.0K-0.1%-0805-0.1W"))
    )
    (comp (ref "R407")
      (value "590")
      (footprint "eagle-import:0805_IPC-7351B")
      (libsource (lib "eagle-import") (part "R0805_IPCR-1.0K-0.1%-0805-0.1W"))
    )
    (comp (ref "R408")
      (value "10K")
      (footprint "eagle-import:0805_IPC-7351B")
      (libsource (lib "eagle-import") (part "R900805_IPCR-1.0K-0.1%-0805-0.1W"))
    )
    (comp (ref "X401")
      (value "W237-102")
      (footprint "eagle-import:W237-102")
      (fields (field (name "MPN") "237-102"))
      (libsource (lib "eagle-import") (part "W237-102"))
    )
    (comp (ref "X402")
      (value "HEATSINK_OMNI_DUAL30-75-D")
      (footprint "eagle-import:OMNI-UNI-30-75-D")
      (libsource (lib "eagle-import") (part "HEATSINK_OMNI_DUAL30-75-D"))
    )
    (comp (ref "C101")
      (value "0.1uF")
      (footprint "eagle-import:0805_IPC-7351B")
      (fields (field (name "PACKAGE") "0805") (field (name "VOLTAGE") "16V") (field (name "BOM") "INCLUDE"))
      (libsource (lib "eagle-import") (part "C0805_IPCC-0.1U-16V-0805-X7R"))
    )
    (comp (ref "C102")
      (value "0.1uF")
      (footprint "eagle-import:0805_IPC-7351B")
      (fields (field (name "PACKAGE") "0805") (field (name "VOLTAGE") "16V") (field (name "BOM") "INCLUDE"))
      (libsource (lib "eagle-import") (part "C0805_IPCC-0.1U-16V-0805-X7R"))
    )
    (comp (ref "C103")
      (value "0.1uF")
      (footprint "eagle-import:0805_IPC-7351B")
      (fields (field (name "PACKAGE") "0805") (field (name "VOLTAGE") "16V") (field (name "BOM") "INCLUDE"))
      (libsource (lib "eagle-import") (part "C0805_IPCC-0.1U-16V-0805-X7R"))
    )
    (comp (ref "C104")
      (value "0.1uF")
      (footprint "eagle-import:0805_IPC-7351B")
      (fields (field (name "PACKAGE") "0805") (field (name "VOLTAGE") "16V") (field (name "BOM") "INCLUDE"))
      (libsource (lib "eagle-import") (part "C0805_IPCC-0.1U-16V-0805-X7R"))
    )
    (comp (ref "C105")
      (value "0.1uF")
      (footprint "eagle-import:0805_IPC-7351B")
      (fields (field (name "PACKAGE") "0805") (field (name "VOLTAGE") "16V") (field (name "BOM") "INCLUDE"))
      (libsource (lib "eagle-import") (part "C0805_IPCC-0.1U-16V-0805-X7R"))
    )
    (comp (ref "C106")
      (value "0.1uF")
      (footprint "eagle-import:0805_IPC-7351B")
      (fields (field (name "PACKAGE") "0805") (field (name "VOLTAGE") "16V") (field (name "BOM") "INCLUDE"))
      (libsource (lib "eagle-import") (part "C0805_IPCC-0.1U-16V-0805-X7R"))
    )
    (comp (ref "C107")
      (value "0.1uF")
      (footprint "eagle-import:0805_IPC-7351B")
      (fields (field (name "PACKAGE") "0805") (field (name "VOLTAGE") "16V") (field (name "BOM") "INCLUDE"))
      (libsource (lib "eagle-import") (part "C0805_IPCC-0.1U-16V-0805-X7R"))
    )
    (comp (ref "C108")
      (value "0.1uF")
      (footprint "eagle-import:0805_IPC-7351B")
      (fields (field (name "VOLTAGE") "16V"))
      (libsource (lib "eagle-import") (part "C0805_IPCC-0.1U-16V-0805-X7R"))
    )
    (comp (ref "C109")
      (value "0.1uF")
      (footprint "eagle-import:0805_IPC-7351B")
      (fields (field (name "VOLTAGE") "16V"))
      (libsource (lib "eagle-import") (part "C0805_IPCC-0.1U-16V-0805-X7R"))
    )
    (comp (ref "C110")
      (value "0.1uF")
      (footprint "eagle-import:0805_IPC-7351B")
      (fields (field (name "VOLTAGE") "16V"))
      (libsource (lib "eagle-import") (part "C0805_IPCC-0.1U-16V-0805-X7R"))
    )
    (comp (ref "C111")
      (value "0.1uF")
      (footprint "eagle-import:0805_IPC-7351B")
      (fields (field (name "VOLTAGE") "16V"))
      (libsource (lib "eagle-import") (part "C0805_IPCC-0.1U-16V-0805-X7R"))
    )
    (comp (ref "C112")
      (value "22nF")
      (footprint "eagle-import:C1206")
      (fields
        (field (name "BOM") "INCLUDE")
        (field (name "PACKAGE") "1206")
        (field (name "PARTNO") "C3216NP02E223J160AA")
        (field (name "VOLTAGE") "250V")
      )
      (libsource (lib "eagle-import") (part "CC1206C-22N-250V-5%-1206-NP0"))
    )
    (comp (ref "C113")
      (value "22nF")
      (footprint "eagle-import:C1206")
      (fields
        (field (name "BOM") "INCLUDE")
        (field (name "PACKAGE") "1206")
        (field (name "PARTNO") "C3216NP02E223J160AA")
        (field (name "VOLTAGE") "250V")
      )
      (libsource (lib "eagle-import") (part "CC1206C-22N-250V-5%-1206-NP0"))
    )
    (comp (ref "C114")
      (value "0.1uF")
      (footprint "eagle-import:0805_IPC-7351B")
      (fields (field (name "VOLTAGE") "16V"))
      (libsource (lib "eagle-import") (part "C0805_IPCC-0.1U-16V-0805-X7R"))
    )
    (comp (ref "C115")
      (value "0.1uF")
      (footprint "eagle-import:0805_IPC-7351B")
      (fields (field (name "VOLTAGE") "16V"))
      (libsource (lib "eagle-import") (part "C0805_IPCC-0.1U-16V-0805-X7R"))
    )
    (comp (ref "C116")
      (value "0.1uF")
      (footprint "eagle-import:C1812")
      (fields (field (name "VOLTAGE") "16V"))
      (libsource (lib "eagle-import") (part "CC1812"))
    )
    (comp (ref "C117")
      (value "0.1uF")
      (footprint "eagle-import:C1812")
      (fields (field (name "VOLTAGE") "16V"))
      (libsource (lib "eagle-import") (part "CC1812"))
    )
    (comp (ref "C118")
      (value "0.1uF")
      (footprint "eagle-import:C1812")
      (fields (field (name "VOLTAGE") "16V") (field (name "PACKAGE") "1812"))
      (libsource (lib "eagle-import") (part "CC1812"))
    )
    (comp (ref "C119")
      (value "0.1uF")
      (footprint "eagle-import:C1812")
      (fields (field (name "VOLTAGE") "16V") (field (name "PACKAGE") "1812"))
      (libsource (lib "eagle-import") (part "CC1812"))
    )
    (comp (ref "C120")
      (value "0.1uF")
      (footprint "eagle-import:C1812")
      (fields (field (name "VOLTAGE") "16V") (field (name "PACKAGE") "1812"))
      (libsource (lib "eagle-import") (part "CC1812"))
    )
    (comp (ref "J101")
      (value "COAXBNC_EDGE")
      (footprint "eagle-import:BNC_EDGE")
      (libsource (lib "eagle-import") (part "COAXBNC_EDGE"))
    )
    (comp (ref "J102")
      (value "COAXBNC_EDGE")
      (footprint "eagle-import:BNC_EDGE")
      (libsource (lib "eagle-import") (part "COAXBNC_EDGE"))
    )
    (comp (ref "L101")
      (value "1uH")
      (footprint "eagle-import:L1008")
      (fields (field (name "PARTNO") "1008CS-102XJEC"))
      (libsource (lib "eagle-import") (part "L_CHIP1008L-1.0U-AIR-5%-1008-0.37A"))
    )
    (comp (ref "L102")
      (value "1uH")
      (footprint "eagle-import:L1008")
      (fields (field (name "PARTNO") "1008CS-102XJEC"))
      (libsource (lib "eagle-import") (part "L_CHIP1008L-1.0U-AIR-5%-1008-0.37A"))
    )
    (comp (ref "L103")
      (value "L")
      (footprint "eagle-import:DR127")
      (libsource (lib "eagle-import") (part "L"))
    )
    (comp (ref "L104")
      (value "L")
      (footprint "eagle-import:DR127")
      (libsource (lib "eagle-import") (part "L"))
    )
    (comp (ref "Q101")
      (value "IRF520N")
      (footprint "eagle-import:TO220BV")
      (libsource (lib "eagle-import") (part "IRF540"))
    )
    (comp (ref "Q102")
      (value "IRF630")
      (footprint "eagle-import:TO220BV")
      (libsource (lib "eagle-import") (part "IRF540"))
    )
    (comp (ref "R101")
      (value "1.0K")
      (footprint "eagle-import:0805_IPC-7351B")
      (libsource (lib "eagle-import") (part "R0805_IPCR-1.0K-0.1%-0805-0.1W"))
    )
    (comp (ref "R102")
      (value "1K")
      (footprint "eagle-import:R1206")
      (fields (field (name "POWER") "0.25"))
      (libsource (lib "eagle-import") (part "RR1206R-1.0K-1%-1206-0.25W"))
    )
    (comp (ref "R103")
      (value "1K")
      (footprint "eagle-import:R1206")
      (fields (field (name "POWER") "0.25"))
      (libsource (lib "eagle-import") (part "RR1206R-1.0K-1%-1206-0.25W"))
    )
    (comp (ref "R104")
      (value "1K")
      (footprint "eagle-import:R1206")
      (fields (field (name "POWER") "0.25"))
      (libsource (lib "eagle-import") (part "RR1206R-1.0K-1%-1206-0.25W"))
    )
    (comp (ref "R105")
      (value "1K")
      (footprint "eagle-import:R1206")
      (fields (field (name "POWER") "0.25"))
      (libsource (lib "eagle-import") (part "RR1206R-1.0K-1%-1206-0.25W"))
    )
    (comp (ref "R106")
      (value "1K")
      (footprint "eagle-import:R1206")
      (fields (field (name "POWER") "0.25"))
      (libsource (lib "eagle-import") (part "RR1206R-1.0K-1%-1206-0.25W"))
    )
    (comp (ref "R107")
      (value "1K")
      (footprint "eagle-import:R1206")
      (fields (field (name "POWER") "0.25"))
      (libsource (lib "eagle-import") (part "RR1206R-1.0K-1%-1206-0.25W"))
    )
    (comp (ref "R108")
      (value "1.0K")
      (footprint "eagle-import:0805_IPC-7351B")
      (libsource (lib "eagle-import") (part "R0805_IPCR-1.0K-0.1%-0805-0.1W"))
    )
    (comp (ref "R109")
      (value "1K")
      (footprint "eagle-import:R1206")
      (fields (field (name "POWER") "0.25"))
      (libsource (lib "eagle-import") (part "RR1206R-1.0K-1%-1206-0.25W"))
    )
    (comp (ref "R110")
      (value "1.0K")
      (footprint "eagle-import:0805_IPC-7351B")
      (libsource (lib "eagle-import") (part "R0805_IPCR-1.0K-0.1%-0805-0.1W"))
    )
    (comp (ref "R111")
      (value "1K")
      (footprint "eagle-import:R1206")
      (fields (field (name "POWER") "0.25"))
      (libsource (lib "eagle-import") (part "RR1206R-1.0K-1%-1206-0.25W"))
    )
    (comp (ref "R112")
      (value "1.0K")
      (footprint "eagle-import:0805_IPC-7351B")
      (libsource (lib "eagle-import") (part "R0805_IPCR-1.0K-0.1%-0805-0.1W"))
    )
    (comp (ref "R113")
      (value "1.0K")
      (footprint "eagle-import:0805_IPC-7351B")
      (libsource (lib "eagle-import") (part "R0805_IPCR-1.0K-0.1%-0805-0.1W"))
    )
    (comp (ref "R114")
      (value "1.0K")
      (footprint "eagle-import:0805_IPC-7351B")
      (libsource (lib "eagle-import") (part "R0805_IPCR-1.0K-0.1%-0805-0.1W"))
    )
    (comp (ref "R115")
      (value "1.0K")
      (footprint "eagle-import:0805_IPC-7351B")
      (libsource (lib "eagle-import") (part "R0805_IPCR-1.0K-0.1%-0805-0.1W"))
    )
    (comp (ref "R116")
      (value "1.0K")
      (footprint "eagle-import:0805_IPC-7351B")
      (libsource (lib "eagle-import") (part "R0805_IPCR-1.0K-0.1%-0805-0.1W"))
    )
    (comp (ref "R117")
      (value "1.0K")
      (footprint "eagle-import:0805_IPC-7351B")
      (libsource (lib "eagle-import") (part "R0805_IPCR-1.0K-0.1%-0805-0.1W"))
    )
    (comp (ref "R118")
      (value "1K")
      (footprint "eagle-import:R2512")
      (fields (field (name "POWER") "1"))
      (libsource (lib "eagle-import") (part "RR2512R-1K-1%-2512-1W"))
    )
    (comp (ref "R119")
      (value "1K")
      (footprint "eagle-import:R2512")
      (fields (field (name "POWER") "1"))
      (libsource (lib "eagle-import") (part "RR2512R-1K-1%-2512-1W"))
    )
    (comp (ref "R120")
      (value "1K")
      (footprint "eagle-import:R2512")
      (fields (field (name "POWER") "1"))
      (libsource (lib "eagle-import") (part "RR2512R-1K-1%-2512-1W"))
    )
    (comp (ref "R121")
      (value "1K")
      (footprint "eagle-import:R2512")
      (fields (field (name "POWER") "1"))
      (libsource (lib "eagle-import") (part "RR2512R-1K-1%-2512-1W"))
    )
    (comp (ref "R122")
      (value "1K")
      (footprint "eagle-import:R2512")
      (fields (field (name "POWER") "1"))
      (libsource (lib "eagle-import") (part "RR2512R-1K-1%-2512-1W"))
    )
    (comp (ref "R123")
      (value "1K")
      (footprint "eagle-import:R2512")
      (fields (field (name "POWER") "1"))
      (libsource (lib "eagle-import") (part "RR2512R-1K-1%-2512-1W"))
    )
    (comp (ref "R124")
      (value "1K")
      (footprint "eagle-import:R2512")
      (fields (field (name "POWER") "1"))
      (libsource (lib "eagle-import") (part "RR2512R-1K-1%-2512-1W"))
    )
    (comp (ref "R125")
      (value "1K")
      (footprint "eagle-import:R2512")
      (fields (field (name "POWER") "1"))
      (libsource (lib "eagle-import") (part "RR2512R-1K-1%-2512-1W"))
    )
    (comp (ref "R126")
      (value "1K")
      (footprint "eagle-import:R2512")
      (fields (field (name "POWER") "1"))
      (libsource (lib "eagle-import") (part "RR2512R-1K-1%-2512-1W"))
    )
    (comp (ref "R127")
      (value "1K")
      (footprint "eagle-import:R2512")
      (fields (field (name "POWER") "1"))
      (libsource (lib "eagle-import") (part "RR2512R-1K-1%-2512-1W"))
    )
    (comp (ref "R128")
      (value "1K")
      (footprint "eagle-import:R2512")
      (fields (field (name "POWER") "1"))
      (libsource (lib "eagle-import") (part "RR2512R-1K-1%-2512-1W"))
    )
    (comp (ref "R129")
      (value "1K")
      (footprint "eagle-import:R2512")
      (fields (field (name "POWER") "1"))
      (libsource (lib "eagle-import") (part "RR2512R-1K-1%-2512-1W"))
    )
    (comp (ref "R130")
      (value "1.0K")
      (footprint "eagle-import:0805_IPC-7351B")
      (fields (field (name "PACKAGE") "0805"))
      (libsource (lib "eagle-import") (part "R0805_IPCR-1.0K-0.1%-0805-0.1W"))
    )
    (comp (ref "R131")
      (value "1.0K")
      (footprint "eagle-import:0805_IPC-7351B")
      (libsource (lib "eagle-import") (part "R0805_IPCR-1.0K-0.1%-0805-0.1W"))
    )
    (comp (ref "R132")
      (value "1.0K")
      (footprint "eagle-import:0805_IPC-7351B")
      (libsource (lib "eagle-import") (part "R0805_IPCR-1.0K-0.1%-0805-0.1W"))
    )
    (comp (ref "T101")
      (value "HP4_TRAFO")
      (footprint "eagle-import:HP4")
      (libsource (lib "eagle-import") (part "HP4_TRAFO"))
    )
    (comp (ref "T102")
      (value "HP4_TRAFO")
      (footprint "eagle-import:HP4")
      (libsource (lib "eagle-import") (part "HP4_TRAFO"))
    )
    (comp (ref "TP1")
      (value "PROBE_TPTP_5MM")
      (footprint "eagle-import:PROBE_TP_5MM")
      (libsource (lib "eagle-import") (part "PROBE_TPTP_5MM"))
    )
    (comp (ref "TP2")
      (value "PROBE_TPTP_7P5MM")
      (footprint "eagle-import:PROBE_TP_7P5MM")
      (libsource (lib "eagle-import") (part "PROBE_TPTP_7P5MM"))
    )
    (comp (ref "TP3")
      (value "PROBE_TPTP_5MM")
      (footprint "eagle-import:PROBE_TP_5MM")
      (libsource (lib "eagle-import") (part "PROBE_TPTP_5MM"))
    )
    (comp (ref "TP4")
      (value "PROBE_TPTP_7P5MM")
      (footprint "eagle-import:PROBE_TP_7P5MM")
      (libsource (lib "eagle-import") (part "PROBE_TPTP_7P5MM"))
    )
    (comp (ref "TP5")
      (value "PROBE_TPTP_7P5MM")
      (footprint "eagle-import:PROBE_TP_7P5MM")
      (libsource (lib "eagle-import") (part "PROBE_TPTP_7P5MM"))
    )
    (comp (ref "TP6")
      (value "PROBE_TPTP_7P5MM")
      (footprint "eagle-import:PROBE_TP_7P5MM")
      (libsource (lib "eagle-import") (part "PROBE_TPTP_7P5MM"))
    )
    (comp (ref "TP14")
      (value "PROBE_TPTP_5MM")
      (footprint "eagle-import:PROBE_TP_5MM")
      (libsource (lib "eagle-import") (part "PROBE_TPTP_5MM"))
    )
    (comp (ref "TP15")
      (value "PROBE_TPTP_5MM")
      (footprint "eagle-import:PROBE_TP_5MM")
      (libsource (lib "eagle-import") (part "PROBE_TPTP_5MM"))
    )
    (comp (ref "TP18")
      (value "PROBE_TPTP_5MM")
      (footprint "eagle-import:PROBE_TP_5MM")
      (libsource (lib "eagle-import") (part "PROBE_TPTP_5MM"))
    )
    (comp (ref "TP19")
      (value "PROBE_TPTP_5MM")
      (footprint "eagle-import:PROBE_TP_5MM")
      (libsource (lib "eagle-import") (part "PROBE_TPTP_5MM"))
    )
  )
  (nets
    (net (code "1") (name "+5V") (class "Default")
      (node (ref "C306") (pin "1") (pinfunction "1_1") (pintype "passive"))
      (node (ref "C407") (pin "1") (pinfunction "1_1") (pintype "passive"))
      (node (ref "C410") (pin "+") (pinfunction "+_+") (pintype "passive"))
      (node (ref "IC301") (pin "5") (pinfunction "VCC_5") (pintype "power_in"))
      (node (ref "IC402") (pin "OUT") (pinfunction "OUT_OUT") (pintype "passive"))
      (node (ref "LED301") (pin "A") (pinfunction "A_A") (pintype "passive"))
      (node (ref "LED402") (pin "A") (pinfunction "A_A") (pintype "passive"))
      (node (ref "R301") (pin "3") (pinfunction "E_3") (pintype "passive"))
      (node (ref "R408") (pin "1") (pinfunction "1_1") (pintype "passive"))
    )
    (net (code "2") (name "+12V") (class "Default")
      (node (ref "C305") (pin "1") (pinfunction "1_1") (pintype "passive"))
      (node (ref "C406") (pin "1") (pinfunction "1_1") (pintype "passive"))
      (node (ref "C409") (pin "+") (pinfunction "+_+") (pintype "passive"))
      (node (ref "IC302") (pin "4") (pinfunction "V+_4") (pintype "power_in"))
      (node (ref "IC401") (pin "OUT") (pinfunction "OUT_OUT") (pintype "passive"))
      (node (ref "J402") (pin "2") (pinfunction "2_2") (pintype "passive"))
      (node (ref "LED401") (pin "A") (pinfunction "A_A") (pintype "passive"))
      (node (ref "T301") (pin "C") (pinfunction "C_C") (pintype "passive"))
    )
    (net (code "3") (name "ABN1") (class "Default")
      (node (ref "R103") (pin "1") (pinfunction "1_1") (pintype "passive"))
      (node (ref "R105") (pin "1") (pinfunction "1_1") (pintype "passive"))
      (node (ref "R202") (pin "1") (pinfunction "1_1") (pintype "passive"))
      (node (ref "R204") (pin "1") (pinfunction "1_1") (pintype "passive"))
      (node (ref "T101") (pin "11") (pinfunction "F2_11") (pintype "passive"))
      (node (ref "TP18") (pin "TP") (pinfunction "1_TP") (pintype "passive"))
    )
    (net (code "4") (name "ABP1") (class "Default")
      (node (ref "R102") (pin "1") (pinfunction "1_1") (pintype "passive"))
      (node (ref "R104") (pin "1") (pinfunction "1_1") (pintype "passive"))
      (node (ref "R201") (pin "1") (pinfunction "1_1") (pintype "passive"))
      (node (ref "R203") (pin "1") (pinfunction "1_1") (pintype "passive"))
      (node (ref "T101") (pin "1") (pinfunction "S1_1") (pintype "passive"))
      (node (ref "TP19") (pin "TP") (pinfunction "1_TP") (pintype "passive"))
    )
    (net (code "5") (name "AN2") (class "Default")
      (node (ref "C107") (pin "2") (pinfunction "2_2") (pintype "passive"))
      (node (ref "R105") (pin "2") (pinfunction "2_2") (pintype "passive"))
      (node (ref "R107") (pin "1") (pinfunction "1_1") (pintype "passive"))
    )
    (net (code "6") (name "AN3") (class "Default")
      (node (ref "C107") (pin "1") (pinfunction "1_1") (pintype "passive"))
      (node (ref "L102") (pin "1") (pinfunction "1_1") (pintype "passive"))
      (node (ref "R111") (pin "2") (pinfunction "2_2") (pintype "passive"))
      (node (ref "R113") (pin "1") (pinfunction "1_1") (pintype "passive"))
      (node (ref "R115") (pin "1") (pinfunction "1_1") (pintype "passive"))
    )
    (net (code "7") (name "AN4") (class "Default")
      (node (ref "L102") (pin "2") (pinfunction "2_2") (pintype "passive"))
      (node (ref "Q102") (pin "G") (pinfunction "G_G") (pintype "passive"))
      (node (ref "R115") (pin "2") (pinfunction "2_2") (pintype "passive"))
      (node (ref "R117") (pin "1") (pinfunction "1_1") (pintype "passive"))
      (node (ref "R120") (pin "1") (pinfunction "1_1") (pintype "passive"))
      (node (ref "R121") (pin "1") (pinfunction "1_1") (pintype "passive"))
      (node (ref "TP3") (pin "TP") (pinfunction "1_TP") (pintype "passive"))
    )
    (net (code "8") (name "AN5") (class "Default")
      (node (ref "Q102") (pin "S") (pinfunction "S_S") (pintype "passive"))
      (node (ref "R123") (pin "1") (pinfunction "1_1") (pintype "passive"))
      (node (ref "R125") (pin "1") (pinfunction "1_1") (pintype "passive"))
      (node (ref "R127") (pin "1") (pinfunction "1_1") (pintype "passive"))
      (node (ref "R129") (pin "1") (pinfunction "1_1") (pintype "passive"))
      (node (ref "R131") (pin "1") (pinfunction "1_1") (pintype "passive"))
      (node (ref "TP6") (pin "TP") (pinfunction "1_TP") (pintype "passive"))
    )
    (net (code "9") (name "AN6") (class "Default")
      (node (ref "C115") (pin "1") (pinfunction "1_1") (pintype "passive"))
      (node (ref "R131") (pin "2") (pinfunction "2_2") (pintype "passive"))
      (node (ref "TP15") (pin "TP") (pinfunction "1_TP") (pintype "passive"))
    )
    (net (code "10") (name "AP2") (class "Default")
      (node (ref "C105") (pin "2") (pinfunction "2_2") (pintype "passive"))
      (node (ref "R104") (pin "2") (pinfunction "2_2") (pintype "passive"))
      (node (ref "R106") (pin "1") (pinfunction "1_1") (pintype "passive"))
    )
    (net (code "11") (name "AP3") (class "Default")
      (node (ref "C105") (pin "1") (pinfunction "1_1") (pintype "passive"))
      (node (ref "L101") (pin "1") (pinfunction "1_1") (pintype "passive"))
      (node (ref "R109") (pin "2") (pinfunction "2_2") (pintype "passive"))
      (node (ref "R112") (pin "1") (pinfunction "1_1") (pintype "passive"))
      (node (ref "R114") (pin "1") (pinfunction "1_1") (pintype "passive"))
    )
    (net (code "12") (name "AP4") (class "Default")
      (node (ref "L101") (pin "2") (pinfunction "2_2") (pintype "passive"))
      (node (ref "Q101") (pin "G") (pinfunction "G_G") (pintype "passive"))
      (node (ref "R114") (pin "2") (pinfunction "2_2") (pintype "passive"))
      (node (ref "R116") (pin "1") (pinfunction "1_1") (pintype "passive"))
      (node (ref "R118") (pin "1") (pinfunction "1_1") (pintype "passive"))
      (node (ref "R119") (pin "1") (pinfunction "1_1") (pintype "passive"))
      (node (ref "TP1") (pin "TP") (pinfunction "1_TP") (pintype "passive"))
    )
    (net (code "13") (name "AP5") (class "Default")
      (node (ref "Q101") (pin "S") (pinfunction "S_S") (pintype "passive"))
      (node (ref "R122") (pin "1") (pinfunction "1_1") (pintype "passive"))
      (node (ref "R124") (pin "1") (pinfunction "1_1") (pintype "passive"))
      (node (ref "R126") (pin "1") (pinfunction "1_1") (pintype "passive"))
      (node (ref "R128") (pin "1") (pinfunction "1_1") (pintype "passive"))
      (node (ref "R130") (pin "1") (pinfunction "1_1") (pintype "passive"))
      (node (ref "TP5") (pin "TP") (pinfunction "1_TP") (pintype "passive"))
    )
    (net (code "14") (name "AP6") (class "Default")
      (node (ref "C114") (pin "1") (pinfunction "1_1") (pintype "passive"))
      (node (ref "R130") (pin "2") (pinfunction "2_2") (pintype "passive"))
      (node (ref "TP14") (pin "TP") (pinfunction "1_TP") (pintype "passive"))
    )
    (net (code "15") (name "BN2") (class "Default")
      (node (ref "C204") (pin "2") (pinfunction "2_2") (pintype "passive"))
      (node (ref "R204") (pin "2") (pinfunction "2_2") (pintype "passive"))
      (node (ref "R206") (pin "1") (pinfunction "1_1") (pintype "passive"))
    )
    (net (code "16") (name "BN3") (class "Default")
      (node (ref "C204") (pin "1") (pinfunction "1_1") (pintype "passive"))
      (node (ref "L202") (pin "1") (pinfunction "1_1") (pintype "passive"))
      (node (ref "R210") (pin "2") (pinfunction "2_2") (pintype "passive"))
      (node (ref "R212") (pin "1") (pinfunction "1_1") (pintype "passive"))
      (node (ref "R214") (pin "1") (pinfunction "1_1") (pintype "passive"))
    )
    (net (code "17") (name "BN4") (class "Default")
      (node (ref "L202") (pin "2") (pinfunction "2_2") (pintype "passive"))
      (node (ref "Q202") (pin "G") (pinfunction "G_G") (pintype "passive"))
      (node (ref "R214") (pin "2") (pinfunction "2_2") (pintype "passive"))
      (node (ref "R216") (pin "1") (pinfunction "1_1") (pintype "passive"))
      (node (ref "R219") (pin "1") (pinfunction "1_1") (pintype "passive"))
      (node (ref "R220") (pin "1") (pinfunction "1_1") (pintype "passive"))
      (node (ref "TP9") (pin "TP") (pinfunction "1_TP") (pintype "passive"))
    )
    (net (code "18") (name "BN5") (class "Default")
      (node (ref "Q202") (pin "S") (pinfunction "S_S") (pintype "passive"))
      (node (ref "R222") (pin "1") (pinfunction "1_1") (pintype "passive"))
      (node (ref "R224") (pin "1") (pinfunction "1_1") (pintype "passive"))
      (node (ref "R226") (pin "1") (pinfunction "1_1") (pintype "passive"))
      (node (ref "R228") (pin "1") (pinfunction "1_1") (pintype "passive"))
      (node (ref "R230") (pin "1") (pinfunction "1_1") (pintype "passive"))
      (node (ref "TP10") (pin "TP") (pinfunction "1_TP") (pintype "passive"))
    )
    (net (code "19") (name "BN6") (class "Default")
      (node (ref "C212") (pin "1") (pinfunction "1_1") (pintype "passive"))
      (node (ref "R230") (pin "2") (pinfunction "2_2") (pintype "passive"))
      (node (ref "TP17") (pin "TP") (pinfunction "1_TP") (pintype "passive"))
    )
    (net (code "20") (name "BP2") (class "Default")
      (node (ref "C202") (pin "2") (pinfunction "2_2") (pintype "passive"))
      (node (ref "R203") (pin "2") (pinfunction "2_2") (pintype "passive"))
      (node (ref "R205") (pin "1") (pinfunction "1_1") (pintype "passive"))
    )
    (net (code "21") (name "BP3") (class "Default")
      (node (ref "C202") (pin "1") (pinfunction "1_1") (pintype "passive"))
      (node (ref "L201") (pin "1") (pinfunction "1_1") (pintype "passive"))
      (node (ref "R208") (pin "2") (pinfunction "2_2") (pintype "passive"))
      (node (ref "R211") (pin "1") (pinfunction "1_1") (pintype "passive"))
      (node (ref "R213") (pin "1") (pinfunction "1_1") (pintype "passive"))
    )
    (net (code "22") (name "BP4") (class "Default")
      (node (ref "L201") (pin "2") (pinfunction "2_2") (pintype "passive"))
      (node (ref "Q201") (pin "G") (pinfunction "G_G") (pintype "passive"))
      (node (ref "R213") (pin "2") (pinfunction "2_2") (pintype "passive"))
      (node (ref "R215") (pin "1") (pinfunction "1_1") (pintype "passive"))
      (node (ref "R217") (pin "1") (pinfunction "1_1") (pintype "passive"))
      (node (ref "R218") (pin "1") (pinfunction "1_1") (pintype "passive"))
      (node (ref "TP7") (pin "TP") (pinfunction "1_TP") (pintype "passive"))
    )
    (net (code "23") (name "BP5") (class "Default")
      (node (ref "Q201") (pin "S") (pinfunction "S_S") (pintype "passive"))
      (node (ref "R221") (pin "1") (pinfunction "1_1") (pintype "passive"))
      (node (ref "R223") (pin "1") (pinfunction "1_1") (pintype "passive"))
      (node (ref "R225") (pin "1") (pinfunction "1_1") (pintype "passive"))
      (node (ref "R227") (pin "1") (pinfunction "1_1") (pintype "passive"))
      (node (ref "R229") (pin "1") (pinfunction "1_1") (pintype "passive"))
      (node (ref "TP8") (pin "TP") (pinfunction "1_TP") (pintype "passive"))
    )
    (net (code "24") (name "BP6") (class "Default")
      (node (ref "C211") (pin "1") (pinfunction "1_1") (pintype "passive"))
      (node (ref "R229") (pin "2") (pinfunction "2_2") (pintype "passive"))
      (node (ref "TP16") (pin "TP") (pinfunction "1_TP") (pintype "passive"))
    )
    (net (code "25") (name "DRAINS_NEG") (class "Default")
      (node (ref "C113") (pin "2") (pinfunction "2_2") (pintype "passive"))
      (node (ref "C117") (pin "2") (pinfunction "2_2") (pintype "passive"))
      (node (ref "C210") (pin "2") (pinfunction "2_2") (pintype "passive"))
      (node (ref "L104") (pin "1") (pinfunction "1_1") (pintype "passive"))
      (node (ref "Q102") (pin "D") (pinfunction "D_D") (pintype "passive"))
      (node (ref "Q202") (pin "D") (pinfunction "D_D") (pintype "passive"))
      (node (ref "T102") (pin "8") (pinfunction "F5_8") (pintype "passive"))
      (node (ref "TP4") (pin "TP") (pinfunction "1_TP") (pintype "passive"))
    )
    (net (code "26") (name "DRAINS_POS") (class "Default")
      (node (ref "C112") (pin "2") (pinfunction "2_2") (pintype "passive"))
      (node (ref "C116") (pin "2") (pinfunction "2_2") (pintype "passive"))
      (node (ref "C209") (pin "2") (pinfunction "2_2") (pintype "passive"))
      (node (ref "L103") (pin "1") (pinfunction "1_1") (pintype "passive"))
      (node (ref "Q101") (pin "D") (pinfunction "D_D") (pintype "passive"))
      (node (ref "Q201") (pin "D") (pinfunction "D_D") (pintype "passive"))
      (node (ref "T102") (pin "6") (pinfunction "S6_6") (pintype "passive"))
      (node (ref "TP2") (pin "TP") (pinfunction "1_TP") (pintype "passive"))
    )
    (net (code "27") (name "GBIAS") (class "Default")
      (node (ref "R108") (pin "1") (pinfunction "1_1") (pintype "passive"))
      (node (ref "R110") (pin "1") (pinfunction "1_1") (pintype "passive"))
      (node (ref "R207") (pin "1") (pinfunction "1_1") (pintype "passive"))
      (node (ref "R209") (pin "1") (pinfunction "1_1") (pintype "passive"))
      (node (ref "R316") (pin "2") (pinfunction "2_2") (pintype "passive"))
      (node (ref "R317") (pin "2") (pinfunction "2_2") (pintype "passive"))
      (node (ref "T301") (pin "E") (pinfunction "E_E") (pintype "passive"))
      (node (ref "T302") (pin "E") (pinfunction "E_E") (pintype "passive"))
      (node (ref "TP11") (pin "TP") (pinfunction "1_TP") (pintype "passive"))
    )
    (net (code "28") (name "GND") (class "Default")
      (node (ref "C104") (pin "2") (pinfunction "2_2") (pintype "passive"))
      (node (ref "C106") (pin "2") (pinfunction "2_2") (pintype "passive"))
      (node (ref "C108") (pin "2") (pinfunction "2_2") (pintype "passive"))
      (node (ref "C109") (pin "2") (pinfunction "2_2") (pintype "passive"))
      (node (ref "C110") (pin "2") (pinfunction "2_2") (pintype "passive"))
      (node (ref "C111") (pin "2") (pinfunction "2_2") (pintype "passive"))
      (node (ref "C114") (pin "2") (pinfunction "2_2") (pintype "passive"))
      (node (ref "C115") (pin "2") (pinfunction "2_2") (pintype "passive"))
      (node (ref "C201") (pin "2") (pinfunction "2_2") (pintype "passive"))
      (node (ref "C203") (pin "2") (pinfunction "2_2") (pintype "passive"))
      (node (ref "C205") (pin "2") (pinfunction "2_2") (pintype "passive"))
      (node (ref "C206") (pin "2") (pinfunction "2_2") (pintype "passive"))
      (node (ref "C207") (pin "2") (pinfunction "2_2") (pintype "passive"))
      (node (ref "C208") (pin "2") (pinfunction "2_2") (pintype "passive"))
      (node (ref "C211") (pin "2") (pinfunction "2_2") (pintype "passive"))
      (node (ref "C212") (pin "2") (pinfunction "2_2") (pintype "passive"))
      (node (ref "C301") (pin "2") (pinfunction "2_2") (pintype "passive"))
      (node (ref "C302") (pin "2") (pinfunction "2_2") (pintype "passive"))
      (node (ref "C303") (pin "2") (pinfunction "2_2") (pintype "passive"))
      (node (ref "C305") (pin "2") (pinfunction "2_2") (pintype "passive"))
      (node (ref "C306") (pin "2") (pinfunction "2_2") (pintype "passive"))
      (node (ref "C401") (pin "-") (pinfunction "-_-") (pintype "passive"))
      (node (ref "C402") (pin "2") (pinfunction "2_2") (pintype "passive"))
      (node (ref "C403") (pin "2") (pinfunction "2_2") (pintype "passive"))
      (node (ref "C404") (pin "2") (pinfunction "2_2") (pintype "passive"))
      (node (ref "C405") (pin "2") (pinfunction "2_2") (pintype "passive"))
      (node (ref "C406") (pin "2") (pinfunction "2_2") (pintype "passive"))
      (node (ref "C407") (pin "2") (pinfunction "2_2") (pintype "passive"))
      (node (ref "C408") (pin "2") (pinfunction "2_2") (pintype "passive"))
      (node (ref "C409") (pin "-") (pinfunction "-_-") (pintype "passive"))
      (node (ref "C410") (pin "-") (pinfunction "-_-") (pintype "passive"))
      (node (ref "C411") (pin "2") (pinfunction "2_2") (pintype "passive"))
      (node (ref "C412") (pin "2") (pinfunction "2_2") (pintype "passive"))
      (node (ref "C413") (pin "2") (pinfunction "2_2") (pintype "passive"))
      (node (ref "D401") (pin "A") (pinfunction "A1_A") (pintype "passive"))
      (node (ref "H401") (pin "B3,2") (pinfunction "MOUNT_B3,2") (pintype "passive"))
      (node (ref "H402") (pin "B3,2") (pinfunction "MOUNT_B3,2") (pintype "passive"))
      (node (ref "H403") (pin "B3,2") (pinfunction "MOUNT_B3,2") (pintype "passive"))
      (node (ref "H404") (pin "B3,2") (pinfunction "MOUNT_B3,2") (pintype "passive"))
      (node (ref "IC301") (pin "3") (pinfunction "GND_3") (pintype "power_in"))
      (node (ref "IC302") (pin "11") (pinfunction "V-_11") (pintype "power_in"))
      (node (ref "IC401") (pin "GND") (pinfunction "GND_GND") (pintype "input"))
      (node (ref "IC402") (pin "GND") (pinfunction "GND_GND") (pintype "input"))
      (node (ref "J101") (pin "G1") (pinfunction "GND1_G1") (pintype "power_in"))
      (node (ref "J101") (pin "G2") (pinfunction "GND1_G2") (pintype "power_in"))
      (node (ref "J101") (pin "G3") (pinfunction "GND1_G3") (pintype "power_in"))
      (node (ref "J101") (pin "G4") (pinfunction "GND1_G4") (pintype "power_in"))
      (node (ref "J102") (pin "G1") (pinfunction "GND1_G1") (pintype "power_in"))
      (node (ref "J102") (pin "G2") (pinfunction "GND1_G2") (pintype "power_in"))
      (node (ref "J102") (pin "G3") (pinfunction "GND1_G3") (pintype "power_in"))
      (node (ref "J102") (pin "G4") (pinfunction "GND1_G4") (pintype "power_in"))
      (node (ref "J302") (pin "G1") (pinfunction "GND1_G1") (pintype "power_in"))
      (node (ref "J302") (pin "G2") (pinfunction "GND1_G2") (pintype "power_in"))
      (node (ref "J302") (pin "G3") (pinfunction "GND1_G3") (pintype "power_in"))
      (node (ref "J302") (pin "G4") (pinfunction "GND1_G4") (pintype "power_in"))
      (node (ref "J402") (pin "1") (pinfunction "1_1") (pintype "passive"))
      (node (ref "Q301") (pin "2") (pinfunction "S_2") (pintype "passive"))
      (node (ref "R101") (pin "2") (pinfunction "2_2") (pintype "passive"))
      (node (ref "R102") (pin "2") (pinfunction "2_2") (pintype "passive"))
      (node (ref "R103") (pin "2") (pinfunction "2_2") (pintype "passive"))
      (node (ref "R106") (pin "2") (pinfunction "2_2") (pintype "passive"))
      (node (ref "R107") (pin "2") (pinfunction "2_2") (pintype "passive"))
      (node (ref "R122") (pin "2") (pinfunction "2_2") (pintype "passive"))
      (node (ref "R123") (pin "2") (pinfunction "2_2") (pintype "passive"))
      (node (ref "R124") (pin "2") (pinfunction "2_2") (pintype "passive"))
      (node (ref "R125") (pin "2") (pinfunction "2_2") (pintype "passive"))
      (node (ref "R126") (pin "2") (pinfunction "2_2") (pintype "passive"))
      (node (ref "R127") (pin "2") (pinfunction "2_2") (pintype "passive"))
      (node (ref "R128") (pin "2") (pinfunction "2_2") (pintype "passive"))
      (node (ref "R129") (pin "2") (pinfunction "2_2") (pintype "passive"))
      (node (ref "R201") (pin "2") (pinfunction "2_2") (pintype "passive"))
      (node (ref "R202") (pin "2") (pinfunction "2_2") (pintype "passive"))
      (node (ref "R205") (pin "2") (pinfunction "2_2") (pintype "passive"))
      (node (ref "R206") (pin "2") (pinfunction "2_2") (pintype "passive"))
      (node (ref "R221") (pin "2") (pinfunction "2_2") (pintype "passive"))
      (node (ref "R222") (pin "2") (pinfunction "2_2") (pintype "passive"))
      (node (ref "R223") (pin "2") (pinfunction "2_2") (pintype "passive"))
      (node (ref "R224") (pin "2") (pinfunction "2_2") (pintype "passive"))
      (node (ref "R225") (pin "2") (pinfunction "2_2") (pintype "passive"))
      (node (ref "R226") (pin "2") (pinfunction "2_2") (pintype "passive"))
      (node (ref "R227") (pin "2") (pinfunction "2_2") (pintype "passive"))
      (node (ref "R228") (pin "2") (pinfunction "2_2") (pintype "passive"))
      (node (ref "R301") (pin "1") (pinfunction "A_1") (pintype "passive"))
      (node (ref "R307") (pin "2") (pinfunction "2_2") (pintype "passive"))
      (node (ref "R311") (pin "2") (pinfunction "2_2") (pintype "passive"))
      (node (ref "R312") (pin "1") (pinfunction "1_1") (pintype "passive"))
      (node (ref "R406") (pin "2") (pinfunction "2_2") (pintype "passive"))
      (node (ref "R407") (pin "2") (pinfunction "2_2") (pintype "passive"))
      (node (ref "T101") (pin "10") (pinfunction "F3_10") (pintype "passive"))
      (node (ref "T102") (pin "9") (pinfunction "F4_9") (pintype "passive"))
      (node (ref "T302") (pin "C") (pinfunction "C_C") (pintype "passive"))
      (node (ref "TP1") (pin "GND") (pinfunction "GND1_GND") (pintype "power_in"))
      (node (ref "TP10") (pin "GND") (pinfunction "GND1_GND") (pintype "power_in"))
      (node (ref "TP11") (pin "GND") (pinfunction "GND1_GND") (pintype "power_in"))
      (node (ref "TP12") (pin "GND") (pinfunction "GND1_GND") (pintype "power_in"))
      (node (ref "TP13") (pin "GND") (pinfunction "GND1_GND") (pintype "power_in"))
      (node (ref "TP14") (pin "GND") (pinfunction "GND1_GND") (pintype "power_in"))
      (node (ref "TP15") (pin "GND") (pinfunction "GND1_GND") (pintype "power_in"))
      (node (ref "TP16") (pin "GND") (pinfunction "GND1_GND") (pintype "power_in"))
      (node (ref "TP17") (pin "GND") (pinfunction "GND1_GND") (pintype "power_in"))
      (node (ref "TP18") (pin "GND") (pinfunction "GND1_GND") (pintype "power_in"))
      (node (ref "TP19") (pin "GND") (pinfunction "GND1_GND") (pintype "power_in"))
      (node (ref "TP2") (pin "GND") (pinfunction "GND1_GND") (pintype "power_in"))
      (node (ref "TP3") (pin "GND") (pinfunction "GND1_GND") (pintype "power_in"))
      (node (ref "TP4") (pin "GND") (pinfunction "GND1_GND") (pintype "power_in"))
      (node (ref "TP5") (pin "GND") (pinfunction "GND1_GND") (pintype "power_in"))
      (node (ref "TP6") (pin "GND") (pinfunction "GND1_GND") (pintype "power_in"))
      (node (ref "TP7") (pin "GND") (pinfunction "GND1_GND") (pintype "power_in"))
      (node (ref "TP8") (pin "GND") (pinfunction "GND1_GND") (pintype "power_in"))
      (node (ref "TP9") (pin "GND") (pinfunction "GND1_GND") (pintype "power_in"))
      (node (ref "X401") (pin "2") (pinfunction "KL_2") (pintype "passive"))
      (node (ref "X402") (pin "P1") (pinfunction "P$1_P1") (pintype "bidirectional"))
      (node (ref "X402") (pin "P2") (pinfunction "P$2_P2") (pintype "bidirectional"))
    )
    (net (code "29") (name "Net-(C104-Pad1)") (class "Default")
      (node (ref "C104") (pin "1") (pinfunction "1_1") (pintype "passive"))
      (node (ref "R108") (pin "2") (pinfunction "2_2") (pintype "passive"))
      (node (ref "R109") (pin "1") (pinfunction "1_1") (pintype "passive"))
    )
    (net (code "30") (name "Net-(C106-Pad1)") (class "Default")
      (node (ref "C106") (pin "1") (pinfunction "1_1") (pintype "passive"))
      (node (ref "R110") (pin "2") (pinfunction "2_2") (pintype "passive"))
      (node (ref "R111") (pin "1") (pinfunction "1_1") (pintype "passive"))
    )
    (net (code "31") (name "Net-(C108-Pad1)") (class "Default")
      (node (ref "C108") (pin "1") (pinfunction "1_1") (pintype "passive"))
      (node (ref "R112") (pin "2") (pinfunction "2_2") (pintype "passive"))
    )
    (net (code "32") (name "Net-(C109-Pad1)") (class "Default")
      (node (ref "C109") (pin "1") (pinfunction "1_1") (pintype "passive"))
      (node (ref "R113") (pin "2") (pinfunction "2_2") (pintype "passive"))
    )
    (net (code "33") (name "Net-(C110-Pad1)") (class "Default")
      (node (ref "C110") (pin "1") (pinfunction "1_1") (pintype "passive"))
      (node (ref "R116") (pin "2") (pinfunction "2_2") (pintype "passive"))
    )
    (net (code "34") (name "Net-(C111-Pad1)") (class "Default")
      (node (ref "C111") (pin "1") (pinfunction "1_1") (pintype "passive"))
      (node (ref "R117") (pin "2") (pinfunction "2_2") (pintype "passive"))
    )
    (net (code "35") (name "Net-(C112-Pad1)") (class "Default")
      (node (ref "C112") (pin "1") (pinfunction "1_1") (pintype "passive"))
      (node (ref "R118") (pin "2") (pinfunction "2_2") (pintype "passive"))
      (node (ref "R119") (pin "2") (pinfunction "2_2") (pintype "passive"))
    )
    (net (code "36") (name "Net-(C113-Pad1)") (class "Default")
      (node (ref "C113") (pin "1") (pinfunction "1_1") (pintype "passive"))
      (node (ref "R120") (pin "2") (pinfunction "2_2") (pintype "passive"))
      (node (ref "R121") (pin "2") (pinfunction "2_2") (pintype "passive"))
    )
    (net (code "37") (name "Net-(C201-Pad1)") (class "Default")
      (node (ref "C201") (pin "1") (pinfunction "1_1") (pintype "passive"))
      (node (ref "R207") (pin "2") (pinfunction "2_2") (pintype "passive"))
      (node (ref "R208") (pin "1") (pinfunction "1_1") (pintype "passive"))
    )
    (net (code "38") (name "Net-(C203-Pad1)") (class "Default")
      (node (ref "C203") (pin "1") (pinfunction "1_1") (pintype "passive"))
      (node (ref "R209") (pin "2") (pinfunction "2_2") (pintype "passive"))
      (node (ref "R210") (pin "1") (pinfunction "1_1") (pintype "passive"))
    )
    (net (code "39") (name "Net-(C205-Pad1)") (class "Default")
      (node (ref "C205") (pin "1") (pinfunction "1_1") (pintype "passive"))
      (node (ref "R211") (pin "2") (pinfunction "2_2") (pintype "passive"))
    )
    (net (code "40") (name "Net-(C206-Pad1)") (class "Default")
      (node (ref "C206") (pin "1") (pinfunction "1_1") (pintype "passive"))
      (node (ref "R212") (pin "2") (pinfunction "2_2") (pintype "passive"))
    )
    (net (code "41") (name "Net-(C207-Pad1)") (class "Default")
      (node (ref "C207") (pin "1") (pinfunction "1_1") (pintype "passive"))
      (node (ref "R215") (pin "2") (pinfunction "2_2") (pintype "passive"))
    )
    (net (code "42") (name "Net-(C208-Pad1)") (class "Default")
      (node (ref "C208") (pin "1") (pinfunction "1_1") (pintype "passive"))
      (node (ref "R216") (pin "2") (pinfunction "2_2") (pintype "passive"))
    )
    (net (code "43") (name "Net-(C209-Pad1)") (class "Default")
      (node (ref "C209") (pin "1") (pinfunction "1_1") (pintype "passive"))
      (node (ref "R217") (pin "2") (pinfunction "2_2") (pintype "passive"))
      (node (ref "R218") (pin "2") (pinfunction "2_2") (pintype "passive"))
    )
    (net (code "44") (name "Net-(C210-Pad1)") (class "Default")
      (node (ref "C210") (pin "1") (pinfunction "1_1") (pintype "passive"))
      (node (ref "R219") (pin "2") (pinfunction "2_2") (pintype "passive"))
      (node (ref "R220") (pin "2") (pinfunction "2_2") (pintype "passive"))
    )
    (net (code "45") (name "Net-(C302-Pad1)") (class "Default")
      (node (ref "C302") (pin "1") (pinfunction "1_1") (pintype "passive"))
      (node (ref "R313") (pin "1") (pinfunction "1_1") (pintype "passive"))
    )
    (net (code "46") (name "Net-(C304-Pad1)") (class "Default")
      (node (ref "C304") (pin "1") (pinfunction "1_1") (pintype "passive"))
      (node (ref "R314") (pin "2") (pinfunction "2_2") (pintype "passive"))
    )
    (net (code "47") (name "Net-(C403-Pad1)") (class "Default")
      (node (ref "C403") (pin "1") (pinfunction "1_1") (pintype "passive"))
      (node (ref "IC401") (pin "IN") (pinfunction "IN_IN") (pintype "input"))
      (node (ref "R402") (pin "2") (pinfunction "2_2") (pintype "passive"))
    )
    (net (code "48") (name "Net-(C404-Pad1)") (class "Default")
      (node (ref "C404") (pin "1") (pinfunction "1_1") (pintype "passive"))
      (node (ref "IC402") (pin "IN") (pinfunction "IN_IN") (pintype "input"))
      (node (ref "R403") (pin "2") (pinfunction "2_2") (pintype "passive"))
    )
    (net (code "49") (name "Net-(C405-Pad1)") (class "Default")
      (node (ref "C405") (pin "1") (pinfunction "1_1") (pintype "passive"))
      (node (ref "L401") (pin "2") (pinfunction "2_2") (pintype "passive"))
      (node (ref "L402") (pin "1") (pinfunction "1_1") (pintype "passive"))
      (node (ref "R404") (pin "1") (pinfunction "1_1") (pintype "passive"))
      (node (ref "R405") (pin "1") (pinfunction "1_1") (pintype "passive"))
    )
    (net (code "50") (name "Net-(D401-C1)") (class "Default")
      (node (ref "D401") (pin "K") (pinfunction "C1_K") (pintype "passive"))
      (node (ref "J401") (pin "2") (pinfunction "2_2") (pintype "passive"))
      (node (ref "R401") (pin "1") (pinfunction "1_1") (pintype "passive"))
    )
    (net (code "51") (name "Net-(D402-A1)") (class "Default")
      (node (ref "D402") (pin "A") (pinfunction "A1_A") (pintype "passive"))
      (node (ref "R402") (pin "1") (pinfunction "1_1") (pintype "passive"))
      (node (ref "R403") (pin "1") (pinfunction "1_1") (pintype "passive"))
    )
    (net (code "52") (name "Net-(D402-C1)") (class "Default")
      (node (ref "C401") (pin "+") (pinfunction "+_+") (pintype "passive"))
      (node (ref "C402") (pin "1") (pinfunction "1_1") (pintype "passive"))
      (node (ref "D402") (pin "C") (pinfunction "C1_C") (pintype "passive"))
      (node (ref "L401") (pin "1") (pinfunction "1_1") (pintype "passive"))
      (node (ref "R401") (pin "2") (pinfunction "2_2") (pintype "passive"))
    )
    (net (code "53") (name "Net-(IC301A-I)") (class "Default")
      (node (ref "IC301") (pin "2") (pinfunction "I_2") (pintype "input"))
      (node (ref "R304") (pin "2") (pinfunction "2_2") (pintype "passive"))
      (node (ref "R307") (pin "1") (pinfunction "1_1") (pintype "passive"))
    )
    (net (code "54") (name "Net-(IC301A-O)") (class "Default")
      (node (ref "IC301") (pin "4") (pinfunction "O_4") (pintype "output"))
      (node (ref "Q301") (pin "1") (pinfunction "G_1") (pintype "passive"))
      (node (ref "R309") (pin "2") (pinfunction "2_2") (pintype "passive"))
    )
    (net (code "55") (name "Net-(IC302A-+IN)") (class "Default")
      (node (ref "C303") (pin "1") (pinfunction "1_1") (pintype "passive"))
      (node (ref "IC302") (pin "3") (pinfunction "+IN_3") (pintype "input"))
      (node (ref "R310") (pin "2") (pinfunction "2_2") (pintype "passive"))
      (node (ref "R311") (pin "1") (pinfunction "1_1") (pintype "passive"))
    )
    (net (code "56") (name "Net-(IC302A--IN)") (class "Default")
      (node (ref "C304") (pin "2") (pinfunction "2_2") (pintype "passive"))
      (node (ref "IC302") (pin "2") (pinfunction "-IN_2") (pintype "input"))
      (node (ref "R312") (pin "2") (pinfunction "2_2") (pintype "passive"))
      (node (ref "R313") (pin "2") (pinfunction "2_2") (pintype "passive"))
      (node (ref "R317") (pin "1") (pinfunction "1_1") (pintype "passive"))
    )
    (net (code "57") (name "Net-(IC302A-OUT)") (class "Default")
      (node (ref "IC302") (pin "1") (pinfunction "OUT_1") (pintype "output"))
      (node (ref "R314") (pin "1") (pinfunction "1_1") (pintype "passive"))
      (node (ref "R315") (pin "1") (pinfunction "1_1") (pintype "passive"))
    )
    (net (code "58") (name "Net-(IC302B-+IN)") (class "Default")
      (node (ref "IC302") (pin "5") (pinfunction "+IN_5") (pintype "input"))
      (node (ref "Q301") (pin "3") (pinfunction "D_3") (pintype "passive"))
      (node (ref "R308") (pin "2") (pinfunction "2_2") (pintype "passive"))
    )
    (net (code "59") (name "Net-(IC302B--IN)") (class "Default")
      (node (ref "IC302") (pin "6") (pinfunction "-IN_6") (pintype "input"))
      (node (ref "IC302") (pin "7") (pinfunction "OUT_7") (pintype "output"))
      (node (ref "R310") (pin "1") (pinfunction "1_1") (pintype "passive"))
      (node (ref "TP12") (pin "TP") (pinfunction "1_TP") (pintype "passive"))
    )
    (net (code "60") (name "Net-(IC302C-+IN)") (class "Default")
      (node (ref "IC302") (pin "10") (pinfunction "+IN_10") (pintype "input"))
      (node (ref "R303") (pin "2") (pinfunction "2_2") (pintype "passive"))
      (node (ref "R306") (pin "1") (pinfunction "1_1") (pintype "passive"))
    )
    (net (code "61") (name "Net-(IC302C--IN)") (class "Default")
      (node (ref "IC302") (pin "9") (pinfunction "-IN_9") (pintype "input"))
      (node (ref "JP302") (pin "1") (pinfunction "1_1") (pintype "passive"))
      (node (ref "R302") (pin "2") (pinfunction "2_2") (pintype "passive"))
      (node (ref "R305") (pin "1") (pinfunction "1_1") (pintype "passive"))
    )
    (net (code "62") (name "Net-(IC302C-OUT)") (class "Default")
      (node (ref "IC302") (pin "8") (pinfunction "OUT_8") (pintype "output"))
      (node (ref "JP302") (pin "2") (pinfunction "2_2") (pintype "passive"))
      (node (ref "R305") (pin "2") (pinfunction "2_2") (pintype "passive"))
      (node (ref "R308") (pin "1") (pinfunction "1_1") (pintype "passive"))
    )
    (net (code "63") (name "Net-(IC302D-+IN)") (class "Default")
      (node (ref "C301") (pin "1") (pinfunction "1_1") (pintype "passive"))
      (node (ref "IC302") (pin "12") (pinfunction "+IN_12") (pintype "input"))
      (node (ref "R301") (pin "2") (pinfunction "S_2") (pintype "passive"))
    )
    (net (code "64") (name "Net-(IC302D--IN)") (class "Default")
      (node (ref "IC302") (pin "13") (pinfunction "-IN_13") (pintype "input"))
      (node (ref "IC302") (pin "14") (pinfunction "OUT_14") (pintype "output"))
      (node (ref "R306") (pin "2") (pinfunction "2_2") (pintype "passive"))
      (node (ref "TP13") (pin "TP") (pinfunction "1_TP") (pintype "passive"))
    )
    (net (code "65") (name "Net-(J101-1)") (class "Default")
      (node (ref "C101") (pin "2") (pinfunction "2_2") (pintype "passive"))
      (node (ref "C102") (pin "2") (pinfunction "2_2") (pintype "passive"))
      (node (ref "C103") (pin "2") (pinfunction "2_2") (pintype "passive"))
      (node (ref "J101") (pin "C") (pinfunction "1_C") (pintype "passive"))
    )
    (net (code "66") (name "Net-(J102-1)") (class "Default")
      (node (ref "C118") (pin "2") (pinfunction "2_2") (pintype "passive"))
      (node (ref "C119") (pin "2") (pinfunction "2_2") (pintype "passive"))
      (node (ref "C120") (pin "2") (pinfunction "2_2") (pintype "passive"))
      (node (ref "J102") (pin "C") (pinfunction "1_C") (pintype "passive"))
    )
    (net (code "67") (name "Net-(J301-1)") (class "Default")
      (node (ref "J301") (pin "C") (pinfunction "1_C") (pintype "passive"))
      (node (ref "JP301") (pin "2") (pinfunction "2_2") (pintype "passive"))
      (node (ref "R302") (pin "1") (pinfunction "1_1") (pintype "passive"))
    )
    (net (code "68") (name "Net-(J301-GND1-PadG1)") (class "Default")
      (node (ref "J301") (pin "G1") (pinfunction "GND1_G1") (pintype "power_in"))
      (node (ref "J301") (pin "G2") (pinfunction "GND1_G2") (pintype "power_in"))
      (node (ref "J301") (pin "G3") (pinfunction "GND1_G3") (pintype "power_in"))
      (node (ref "J301") (pin "G4") (pinfunction "GND1_G4") (pintype "power_in"))
      (node (ref "JP301") (pin "1") (pinfunction "1_1") (pintype "passive"))
      (node (ref "R303") (pin "1") (pinfunction "1_1") (pintype "passive"))
    )
    (net (code "69") (name "Net-(J302-1)") (class "Default")
      (node (ref "J302") (pin "C") (pinfunction "1_C") (pintype "passive"))
      (node (ref "R304") (pin "1") (pinfunction "1_1") (pintype "passive"))
    )
    (net (code "70") (name "Net-(J402-Pad3)") (class "Default")
      (node (ref "J402") (pin "3") (pinfunction "3_3") (pintype "passive"))
      (node (ref "R408") (pin "2") (pinfunction "2_2") (pintype "passive"))
    )
    (net (code "71") (name "Net-(LED301-C)") (class "Default")
      (node (ref "LED301") (pin "K") (pinfunction "C_K") (pintype "passive"))
      (node (ref "R309") (pin "1") (pinfunction "1_1") (pintype "passive"))
    )
    (net (code "72") (name "Net-(LED401-C)") (class "Default")
      (node (ref "LED401") (pin "K") (pinfunction "C_K") (pintype "passive"))
      (node (ref "R406") (pin "1") (pinfunction "1_1") (pintype "passive"))
    )
    (net (code "73") (name "Net-(LED402-C)") (class "Default")
      (node (ref "LED402") (pin "K") (pinfunction "C_K") (pintype "passive"))
      (node (ref "R407") (pin "1") (pinfunction "1_1") (pintype "passive"))
    )
    (net (code "74") (name "Net-(R315-Pad2)") (class "Default")
      (node (ref "R315") (pin "2") (pinfunction "2_2") (pintype "passive"))
      (node (ref "R316") (pin "1") (pinfunction "1_1") (pintype "passive"))
      (node (ref "T301") (pin "B") (pinfunction "B_B") (pintype "passive"))
      (node (ref "T302") (pin "B") (pinfunction "B_B") (pintype "passive"))
    )
    (net (code "75") (name "Net-(T101-F1)") (class "Default")
      (node (ref "R101") (pin "1") (pinfunction "1_1") (pintype "passive"))
      (node (ref "T101") (pin "12") (pinfunction "F1_12") (pintype "passive"))
      (node (ref "T101") (pin "2") (pinfunction "S2_2") (pintype "passive"))
    )
    (net (code "76") (name "Net-(T101-F4)") (class "Default")
      (node (ref "T101") (pin "3") (pinfunction "S3_3") (pintype "passive"))
      (node (ref "T101") (pin "9") (pinfunction "F4_9") (pintype "passive"))
    )
    (net (code "77") (name "Net-(T101-F5)") (class "Default")
      (node (ref "C101") (pin "1") (pinfunction "1_1") (pintype "passive"))
      (node (ref "T101") (pin "4") (pinfunction "S4_4") (pintype "passive"))
      (node (ref "T101") (pin "8") (pinfunction "F5_8") (pintype "passive"))
    )
    (net (code "78") (name "Net-(T101-F6)") (class "Default")
      (node (ref "C102") (pin "1") (pinfunction "1_1") (pintype "passive"))
      (node (ref "T101") (pin "5") (pinfunction "S5_5") (pintype "passive"))
      (node (ref "T101") (pin "7") (pinfunction "F6_7") (pintype "passive"))
    )
    (net (code "79") (name "Net-(T101-S6)") (class "Default")
      (node (ref "C103") (pin "1") (pinfunction "1_1") (pintype "passive"))
      (node (ref "T101") (pin "6") (pinfunction "S6_6") (pintype "passive"))
    )
    (net (code "80") (name "Net-(T102-F1)") (class "Default")
      (node (ref "C119") (pin "1") (pinfunction "1_1") (pintype "passive"))
      (node (ref "T102") (pin "12") (pinfunction "F1_12") (pintype "passive"))
      (node (ref "T102") (pin "2") (pinfunction "S2_2") (pintype "passive"))
    )
    (net (code "81") (name "Net-(T102-F2)") (class "Default")
      (node (ref "C118") (pin "1") (pinfunction "1_1") (pintype "passive"))
      (node (ref "T102") (pin "11") (pinfunction "F2_11") (pintype "passive"))
      (node (ref "T102") (pin "3") (pinfunction "S3_3") (pintype "passive"))
    )
    (net (code "82") (name "Net-(T102-F3)") (class "Default")
      (node (ref "T102") (pin "10") (pinfunction "F3_10") (pintype "passive"))
      (node (ref "T102") (pin "4") (pinfunction "S4_4") (pintype "passive"))
    )
    (net (code "83") (name "Net-(T102-F6)") (class "Default")
      (node (ref "R132") (pin "2") (pinfunction "2_2") (pintype "passive"))
      (node (ref "T102") (pin "5") (pinfunction "S5_5") (pintype "passive"))
      (node (ref "T102") (pin "7") (pinfunction "F6_7") (pintype "passive"))
    )
    (net (code "84") (name "Net-(T102-S1)") (class "Default")
      (node (ref "C120") (pin "1") (pinfunction "1_1") (pintype "passive"))
      (node (ref "T102") (pin "1") (pinfunction "S1_1") (pintype "passive"))
    )
    (net (code "85") (name "Net-(X401A-KL)") (class "Default")
      (node (ref "J401") (pin "1") (pinfunction "1_1") (pintype "passive"))
      (node (ref "X401") (pin "1") (pinfunction "KL_1") (pintype "passive"))
    )
    (net (code "86") (name "VB") (class "Default")
      (node (ref "C116") (pin "1") (pinfunction "1_1") (pintype "passive"))
      (node (ref "C117") (pin "1") (pinfunction "1_1") (pintype "passive"))
      (node (ref "C408") (pin "1") (pinfunction "1_1") (pintype "passive"))
      (node (ref "C411") (pin "1") (pinfunction "1_1") (pintype "passive"))
      (node (ref "C412") (pin "1") (pinfunction "1_1") (pintype "passive"))
      (node (ref "C413") (pin "1") (pinfunction "1_1") (pintype "passive"))
      (node (ref "L103") (pin "2") (pinfunction "2_2") (pintype "passive"))
      (node (ref "L104") (pin "2") (pinfunction "2_2") (pintype "passive"))
      (node (ref "L402") (pin "2") (pinfunction "2_2") (pintype "passive"))
      (node (ref "R132") (pin "1") (pinfunction "1_1") (pintype "passive"))
      (node (ref "R404") (pin "2") (pinfunction "2_2") (pintype "passive"))
      (node (ref "R405") (pin "2") (pinfunction "2_2") (pintype "passive"))
    )
    (net (code "87") (name "unconnected-(J402-Pad4)") (class "Default")
      (node (ref "J402") (pin "4") (pinfunction "4_4") (pintype "passive"))
    )
  )
)
